# powermax.net
KiCad netlist of a schematic drawn in EAGLE
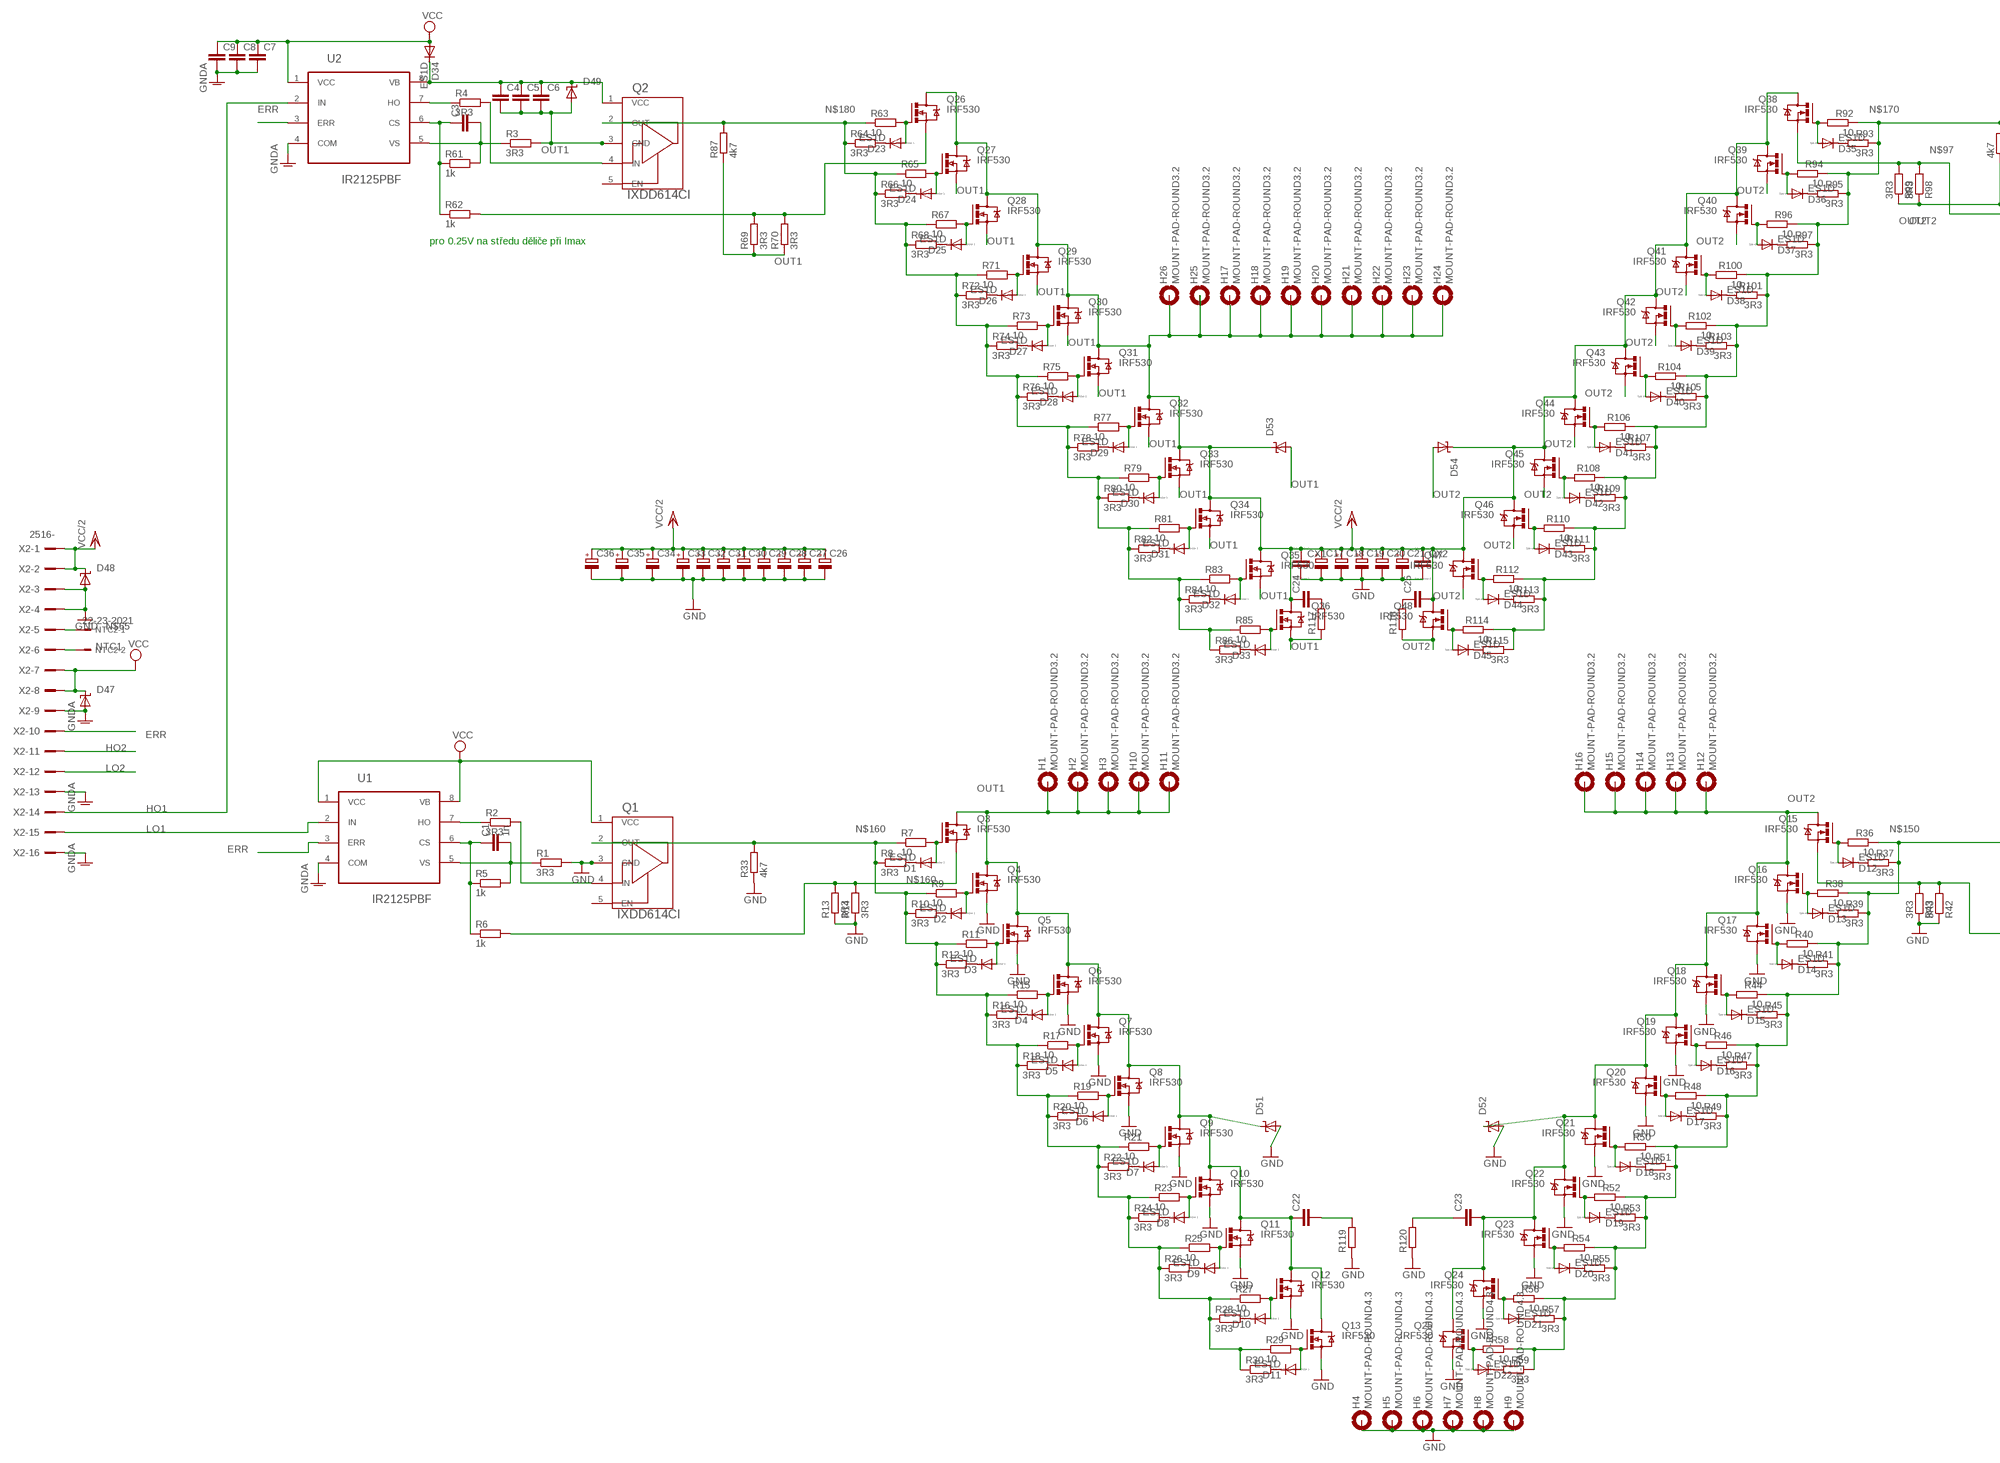
[diagram p0: schematic, sheet 1, part 1 of 2]
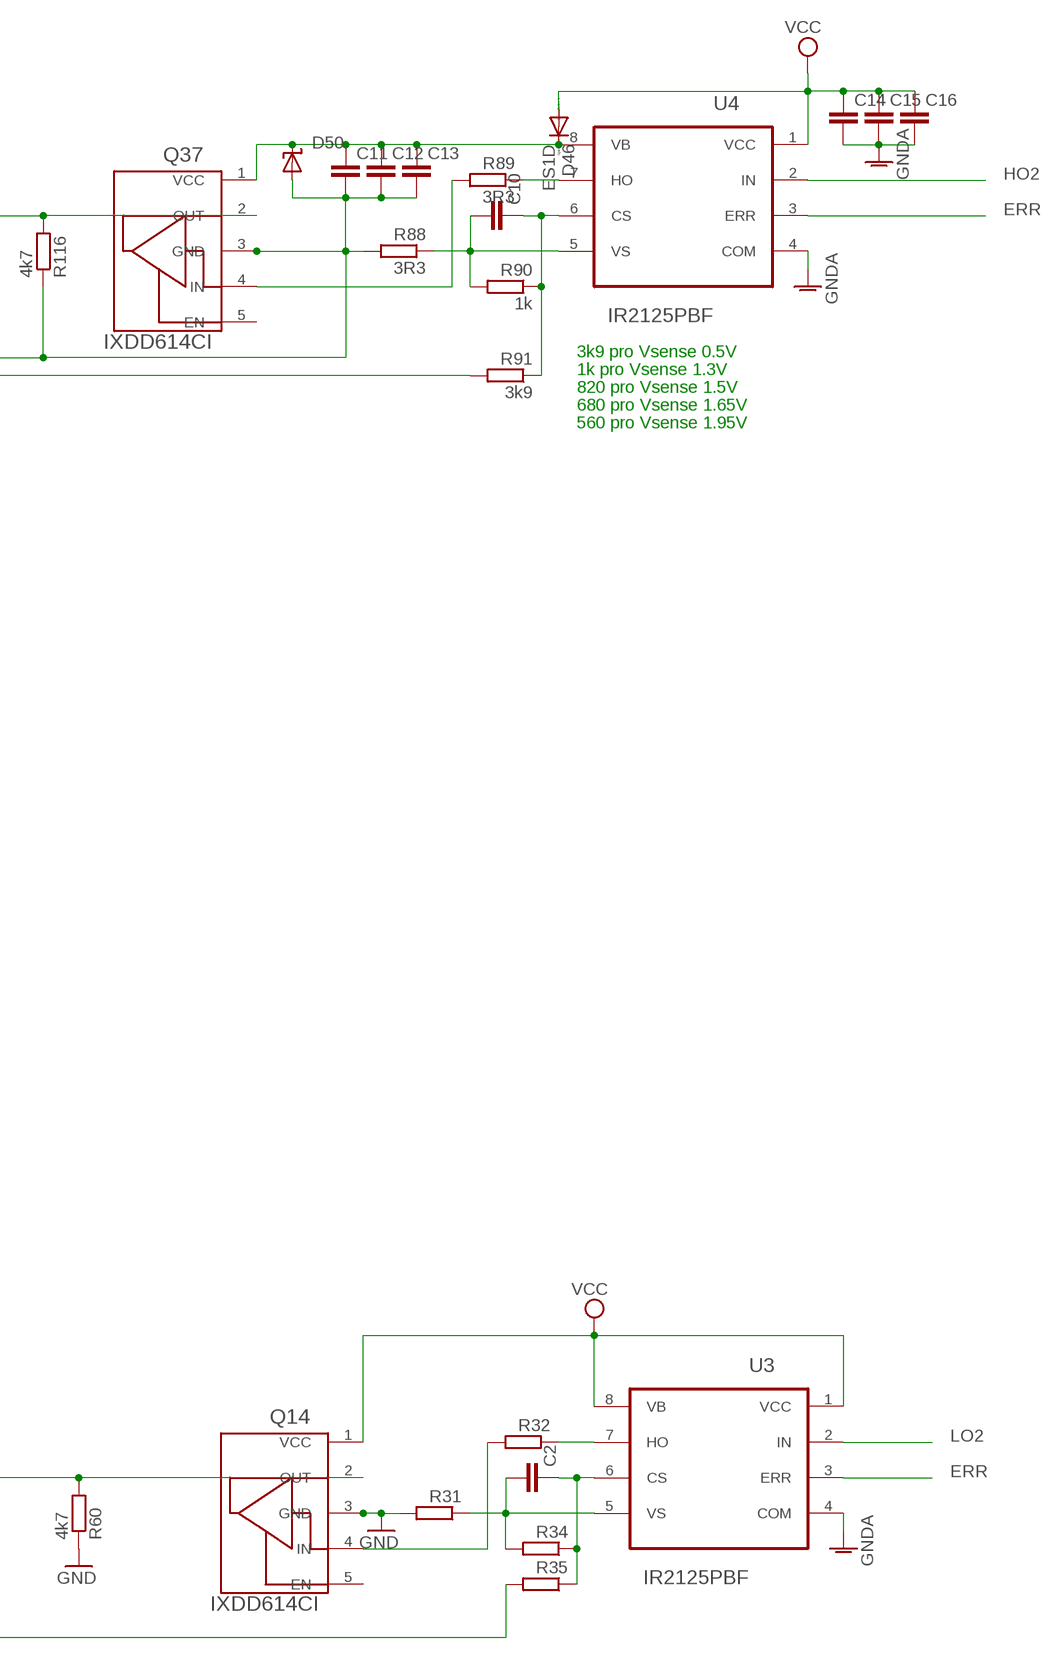
[diagram p1: schematic, sheet 1, part 2 of 2]

(export (version "E")
  (design (tool "Eeschema 10.0.6"))
  (components
    (comp (ref "C1")
      (value "1n")
      (footprint "eagle-import:C0805")
      (libsource (lib "eagle-import") (part "C-EUC0805"))
    )
    (comp (ref "C2")
      (value "C-EUC0805")
      (footprint "eagle-import:C0805")
      (libsource (lib "eagle-import") (part "C-EUC0805"))
    )
    (comp (ref "C3")
      (value "C-EUC0805")
      (footprint "eagle-import:C0805")
      (libsource (lib "eagle-import") (part "C-EUC0805"))
    )
    (comp (ref "C4")
      (value "C-EUC1210")
      (footprint "eagle-import:C1210")
      (libsource (lib "eagle-import") (part "C-EUC1210"))
    )
    (comp (ref "C5")
      (value "C-EUC1210")
      (footprint "eagle-import:C1210")
      (libsource (lib "eagle-import") (part "C-EUC1210"))
    )
    (comp (ref "C6")
      (value "C-EUC1210")
      (footprint "eagle-import:C1210")
      (libsource (lib "eagle-import") (part "C-EUC1210"))
    )
    (comp (ref "C7")
      (value "C-EUC1210")
      (footprint "eagle-import:C1210")
      (libsource (lib "eagle-import") (part "C-EUC1210"))
    )
    (comp (ref "C8")
      (value "C-EUC1210")
      (footprint "eagle-import:C1210")
      (libsource (lib "eagle-import") (part "C-EUC1210"))
    )
    (comp (ref "C9")
      (value "C-EUC1210")
      (footprint "eagle-import:C1210")
      (libsource (lib "eagle-import") (part "C-EUC1210"))
    )
    (comp (ref "C10")
      (value "C-EUC0805")
      (footprint "eagle-import:C0805")
      (libsource (lib "eagle-import") (part "C-EUC0805"))
    )
    (comp (ref "C11")
      (value "C-EUC1210")
      (footprint "eagle-import:C1210")
      (libsource (lib "eagle-import") (part "C-EUC1210"))
    )
    (comp (ref "C12")
      (value "C-EUC1210")
      (footprint "eagle-import:C1210")
      (libsource (lib "eagle-import") (part "C-EUC1210"))
    )
    (comp (ref "C13")
      (value "C-EUC1210")
      (footprint "eagle-import:C1210")
      (libsource (lib "eagle-import") (part "C-EUC1210"))
    )
    (comp (ref "C14")
      (value "C-EUC1210")
      (footprint "eagle-import:C1210")
      (libsource (lib "eagle-import") (part "C-EUC1210"))
    )
    (comp (ref "C15")
      (value "C-EUC1210")
      (footprint "eagle-import:C1210")
      (libsource (lib "eagle-import") (part "C-EUC1210"))
    )
    (comp (ref "C16")
      (value "C-EUC1210")
      (footprint "eagle-import:C1210")
      (libsource (lib "eagle-import") (part "C-EUC1210"))
    )
    (comp (ref "C17")
      (value "CPOL-EUE10-35")
      (footprint "eagle-import:EB35D")
      (libsource (lib "eagle-import") (part "CPOL-EUE10-35"))
    )
    (comp (ref "C18")
      (value "CPOL-EUE10-35")
      (footprint "eagle-import:EB35D")
      (libsource (lib "eagle-import") (part "CPOL-EUE10-35"))
    )
    (comp (ref "C19")
      (value "CPOL-EUE10-35")
      (footprint "eagle-import:EB35D")
      (libsource (lib "eagle-import") (part "CPOL-EUE10-35"))
    )
    (comp (ref "C20")
      (value "CPOL-EUE10-35")
      (footprint "eagle-import:EB35D")
      (libsource (lib "eagle-import") (part "CPOL-EUE10-35"))
    )
    (comp (ref "C21")
      (value "CPOL-EUE10-35")
      (footprint "eagle-import:EB35D")
      (libsource (lib "eagle-import") (part "CPOL-EUE10-35"))
    )
    (comp (ref "C22")
      (value "C-EU225-113X268")
      (footprint "eagle-import:C225-113X268")
      (libsource (lib "eagle-import") (part "C-EU225-113X268"))
    )
    (comp (ref "C23")
      (value "C-EU225-113X268")
      (footprint "eagle-import:C225-113X268")
      (libsource (lib "eagle-import") (part "C-EU225-113X268"))
    )
    (comp (ref "C24")
      (value "C-EU225-113X268")
      (footprint "eagle-import:C225-113X268")
      (libsource (lib "eagle-import") (part "C-EU225-113X268"))
    )
    (comp (ref "C25")
      (value "C-EU225-113X268")
      (footprint "eagle-import:C225-113X268")
      (libsource (lib "eagle-import") (part "C-EU225-113X268"))
    )
    (comp (ref "C26")
      (value "CPOL-EUE7.5-18")
      (footprint "eagle-import:E7,5-18")
      (libsource (lib "eagle-import") (part "CPOL-EUE7.5-18"))
    )
    (comp (ref "C27")
      (value "CPOL-EUE7.5-18")
      (footprint "eagle-import:E7,5-18")
      (libsource (lib "eagle-import") (part "CPOL-EUE7.5-18"))
    )
    (comp (ref "C28")
      (value "CPOL-EUE7.5-18")
      (footprint "eagle-import:E7,5-18")
      (libsource (lib "eagle-import") (part "CPOL-EUE7.5-18"))
    )
    (comp (ref "C29")
      (value "CPOL-EUE7.5-18")
      (footprint "eagle-import:E7,5-18")
      (libsource (lib "eagle-import") (part "CPOL-EUE7.5-18"))
    )
    (comp (ref "C30")
      (value "CPOL-EUE7.5-18")
      (footprint "eagle-import:E7,5-18")
      (libsource (lib "eagle-import") (part "CPOL-EUE7.5-18"))
    )
    (comp (ref "C31")
      (value "CPOL-EUE7.5-18")
      (footprint "eagle-import:E7,5-18")
      (libsource (lib "eagle-import") (part "CPOL-EUE7.5-18"))
    )
    (comp (ref "C32")
      (value "CPOL-EUE7.5-18")
      (footprint "eagle-import:E7,5-18")
      (libsource (lib "eagle-import") (part "CPOL-EUE7.5-18"))
    )
    (comp (ref "C33")
      (value "CPOL-EUE7.5-18")
      (footprint "eagle-import:E7,5-18")
      (libsource (lib "eagle-import") (part "CPOL-EUE7.5-18"))
    )
    (comp (ref "C34")
      (value "CPOL-EUE7.5-18")
      (footprint "eagle-import:E7,5-18")
      (libsource (lib "eagle-import") (part "CPOL-EUE7.5-18"))
    )
    (comp (ref "C35")
      (value "CPOL-EUE7.5-18")
      (footprint "eagle-import:E7,5-18")
      (libsource (lib "eagle-import") (part "CPOL-EUE7.5-18"))
    )
    (comp (ref "C36")
      (value "CPOL-EUE7.5-18")
      (footprint "eagle-import:E7,5-18")
      (libsource (lib "eagle-import") (part "CPOL-EUE7.5-18"))
    )
    (comp (ref "CX1")
      (value "CXXC27B11")
      (footprint "eagle-import:XC27B11")
      (libsource (lib "eagle-import") (part "CXXC27B11"))
    )
    (comp (ref "CX2")
      (value "CXXC27B11")
      (footprint "eagle-import:XC27B11")
      (libsource (lib "eagle-import") (part "CXXC27B11"))
    )
    (comp (ref "D1")
      (value "ES1D")
      (footprint "eagle-import:SOD80C")
      (libsource (lib "eagle-import") (part "PMLL4150"))
    )
    (comp (ref "D2")
      (value "ES1D")
      (footprint "eagle-import:SOD80C")
      (libsource (lib "eagle-import") (part "PMLL4150"))
    )
    (comp (ref "D3")
      (value "ES1D")
      (footprint "eagle-import:SOD80C")
      (libsource (lib "eagle-import") (part "PMLL4150"))
    )
    (comp (ref "D4")
      (value "ES1D")
      (footprint "eagle-import:SOD80C")
      (libsource (lib "eagle-import") (part "PMLL4150"))
    )
    (comp (ref "D5")
      (value "ES1D")
      (footprint "eagle-import:SOD80C")
      (libsource (lib "eagle-import") (part "PMLL4150"))
    )
    (comp (ref "D6")
      (value "ES1D")
      (footprint "eagle-import:SOD80C")
      (libsource (lib "eagle-import") (part "PMLL4150"))
    )
    (comp (ref "D7")
      (value "ES1D")
      (footprint "eagle-import:SOD80C")
      (libsource (lib "eagle-import") (part "PMLL4150"))
    )
    (comp (ref "D8")
      (value "ES1D")
      (footprint "eagle-import:SOD80C")
      (libsource (lib "eagle-import") (part "PMLL4150"))
    )
    (comp (ref "D9")
      (value "ES1D")
      (footprint "eagle-import:SOD80C")
      (libsource (lib "eagle-import") (part "PMLL4150"))
    )
    (comp (ref "D10")
      (value "ES1D")
      (footprint "eagle-import:SOD80C")
      (libsource (lib "eagle-import") (part "PMLL4150"))
    )
    (comp (ref "D11")
      (value "ES1D")
      (footprint "eagle-import:SOD80C")
      (libsource (lib "eagle-import") (part "PMLL4150"))
    )
    (comp (ref "D12")
      (value "ES1D")
      (footprint "eagle-import:SOD80C")
      (libsource (lib "eagle-import") (part "PMLL4150"))
    )
    (comp (ref "D13")
      (value "ES1D")
      (footprint "eagle-import:SOD80C")
      (libsource (lib "eagle-import") (part "PMLL4150"))
    )
    (comp (ref "D14")
      (value "ES1D")
      (footprint "eagle-import:SOD80C")
      (libsource (lib "eagle-import") (part "PMLL4150"))
    )
    (comp (ref "D15")
      (value "ES1D")
      (footprint "eagle-import:SOD80C")
      (libsource (lib "eagle-import") (part "PMLL4150"))
    )
    (comp (ref "D16")
      (value "ES1D")
      (footprint "eagle-import:SOD80C")
      (libsource (lib "eagle-import") (part "PMLL4150"))
    )
    (comp (ref "D17")
      (value "ES1D")
      (footprint "eagle-import:SOD80C")
      (libsource (lib "eagle-import") (part "PMLL4150"))
    )
    (comp (ref "D18")
      (value "ES1D")
      (footprint "eagle-import:SOD80C")
      (libsource (lib "eagle-import") (part "PMLL4150"))
    )
    (comp (ref "D19")
      (value "ES1D")
      (footprint "eagle-import:SOD80C")
      (libsource (lib "eagle-import") (part "PMLL4150"))
    )
    (comp (ref "D20")
      (value "ES1D")
      (footprint "eagle-import:SOD80C")
      (libsource (lib "eagle-import") (part "PMLL4150"))
    )
    (comp (ref "D21")
      (value "ES1D")
      (footprint "eagle-import:SOD80C")
      (libsource (lib "eagle-import") (part "PMLL4150"))
    )
    (comp (ref "D22")
      (value "ES1D")
      (footprint "eagle-import:SOD80C")
      (libsource (lib "eagle-import") (part "PMLL4150"))
    )
    (comp (ref "D23")
      (value "ES1D")
      (footprint "eagle-import:SOD80C")
      (libsource (lib "eagle-import") (part "PMLL4150"))
    )
    (comp (ref "D24")
      (value "ES1D")
      (footprint "eagle-import:SOD80C")
      (libsource (lib "eagle-import") (part "PMLL4150"))
    )
    (comp (ref "D25")
      (value "ES1D")
      (footprint "eagle-import:SOD80C")
      (libsource (lib "eagle-import") (part "PMLL4150"))
    )
    (comp (ref "D26")
      (value "ES1D")
      (footprint "eagle-import:SOD80C")
      (libsource (lib "eagle-import") (part "PMLL4150"))
    )
    (comp (ref "D27")
      (value "ES1D")
      (footprint "eagle-import:SOD80C")
      (libsource (lib "eagle-import") (part "PMLL4150"))
    )
    (comp (ref "D28")
      (value "ES1D")
      (footprint "eagle-import:SOD80C")
      (libsource (lib "eagle-import") (part "PMLL4150"))
    )
    (comp (ref "D29")
      (value "ES1D")
      (footprint "eagle-import:SOD80C")
      (libsource (lib "eagle-import") (part "PMLL4150"))
    )
    (comp (ref "D30")
      (value "ES1D")
      (footprint "eagle-import:SOD80C")
      (libsource (lib "eagle-import") (part "PMLL4150"))
    )
    (comp (ref "D31")
      (value "ES1D")
      (footprint "eagle-import:SOD80C")
      (libsource (lib "eagle-import") (part "PMLL4150"))
    )
    (comp (ref "D32")
      (value "ES1D")
      (footprint "eagle-import:SOD80C")
      (libsource (lib "eagle-import") (part "PMLL4150"))
    )
    (comp (ref "D33")
      (value "ES1D")
      (footprint "eagle-import:SOD80C")
      (libsource (lib "eagle-import") (part "PMLL4150"))
    )
    (comp (ref "D34")
      (value "ES1D")
      (footprint "eagle-import:SOD80C")
      (libsource (lib "eagle-import") (part "PMLL4150"))
    )
    (comp (ref "D35")
      (value "ES1D")
      (footprint "eagle-import:SOD80C")
      (libsource (lib "eagle-import") (part "PMLL4150"))
    )
    (comp (ref "D36")
      (value "ES1D")
      (footprint "eagle-import:SOD80C")
      (libsource (lib "eagle-import") (part "PMLL4150"))
    )
    (comp (ref "D37")
      (value "ES1D")
      (footprint "eagle-import:SOD80C")
      (libsource (lib "eagle-import") (part "PMLL4150"))
    )
    (comp (ref "D38")
      (value "ES1D")
      (footprint "eagle-import:SOD80C")
      (libsource (lib "eagle-import") (part "PMLL4150"))
    )
    (comp (ref "D39")
      (value "ES1D")
      (footprint "eagle-import:SOD80C")
      (libsource (lib "eagle-import") (part "PMLL4150"))
    )
    (comp (ref "D40")
      (value "ES1D")
      (footprint "eagle-import:SOD80C")
      (libsource (lib "eagle-import") (part "PMLL4150"))
    )
    (comp (ref "D41")
      (value "ES1D")
      (footprint "eagle-import:SOD80C")
      (libsource (lib "eagle-import") (part "PMLL4150"))
    )
    (comp (ref "D42")
      (value "ES1D")
      (footprint "eagle-import:SOD80C")
      (libsource (lib "eagle-import") (part "PMLL4150"))
    )
    (comp (ref "D43")
      (value "ES1D")
      (footprint "eagle-import:SOD80C")
      (libsource (lib "eagle-import") (part "PMLL4150"))
    )
    (comp (ref "D44")
      (value "ES1D")
      (footprint "eagle-import:SOD80C")
      (libsource (lib "eagle-import") (part "PMLL4150"))
    )
    (comp (ref "D45")
      (value "ES1D")
      (footprint "eagle-import:SOD80C")
      (libsource (lib "eagle-import") (part "PMLL4150"))
    )
    (comp (ref "D46")
      (value "ES1D")
      (footprint "eagle-import:SOD80C")
      (libsource (lib "eagle-import") (part "PMLL4150"))
    )
    (comp (ref "D47")
      (value "SUPPRESSOR-SMBJ")
      (footprint "eagle-import:SMBJ")
      (libsource (lib "eagle-import") (part "SUPPRESSOR-SMBJ"))
    )
    (comp (ref "D48")
      (value "SUPPRESSOR-SMBJ")
      (footprint "eagle-import:SMBJ")
      (libsource (lib "eagle-import") (part "SUPPRESSOR-SMBJ"))
    )
    (comp (ref "D49")
      (value "SUPPRESSOR-SMBJ")
      (footprint "eagle-import:SMBJ")
      (libsource (lib "eagle-import") (part "SUPPRESSOR-SMBJ"))
    )
    (comp (ref "D50")
      (value "SUPPRESSOR-SMBJ")
      (footprint "eagle-import:SMBJ")
      (libsource (lib "eagle-import") (part "SUPPRESSOR-SMBJ"))
    )
    (comp (ref "D51")
      (value "SUPPRESSOR-SMBJ")
      (footprint "eagle-import:SMBJ")
      (libsource (lib "eagle-import") (part "SUPPRESSOR-SMBJ"))
    )
    (comp (ref "D52")
      (value "SUPPRESSOR-SMBJ")
      (footprint "eagle-import:SMBJ")
      (libsource (lib "eagle-import") (part "SUPPRESSOR-SMBJ"))
    )
    (comp (ref "D53")
      (value "SUPPRESSOR-SMBJ")
      (footprint "eagle-import:SMBJ")
      (libsource (lib "eagle-import") (part "SUPPRESSOR-SMBJ"))
    )
    (comp (ref "D54")
      (value "SUPPRESSOR-SMBJ")
      (footprint "eagle-import:SMBJ")
      (libsource (lib "eagle-import") (part "SUPPRESSOR-SMBJ"))
    )
    (comp (ref "H1")
      (value "MOUNT-PAD-ROUND3.2")
      (footprint "eagle-import:3,2-PAD")
      (libsource (lib "eagle-import") (part "MOUNT-PAD-ROUND3.2"))
    )
    (comp (ref "H2")
      (value "MOUNT-PAD-ROUND3.2")
      (footprint "eagle-import:3,2-PAD")
      (libsource (lib "eagle-import") (part "MOUNT-PAD-ROUND3.2"))
    )
    (comp (ref "H3")
      (value "MOUNT-PAD-ROUND3.2")
      (footprint "eagle-import:3,2-PAD")
      (libsource (lib "eagle-import") (part "MOUNT-PAD-ROUND3.2"))
    )
    (comp (ref "H4")
      (value "MOUNT-PAD-ROUND4.3")
      (footprint "eagle-import:4,3-PAD")
      (libsource (lib "eagle-import") (part "MOUNT-PAD-ROUND4.3"))
    )
    (comp (ref "H5")
      (value "MOUNT-PAD-ROUND4.3")
      (footprint "eagle-import:4,3-PAD")
      (libsource (lib "eagle-import") (part "MOUNT-PAD-ROUND4.3"))
    )
    (comp (ref "H6")
      (value "MOUNT-PAD-ROUND4.3")
      (footprint "eagle-import:4,3-PAD")
      (libsource (lib "eagle-import") (part "MOUNT-PAD-ROUND4.3"))
    )
    (comp (ref "H7")
      (value "MOUNT-PAD-ROUND4.3")
      (footprint "eagle-import:4,3-PAD")
      (libsource (lib "eagle-import") (part "MOUNT-PAD-ROUND4.3"))
    )
    (comp (ref "H8")
      (value "MOUNT-PAD-ROUND4.3")
      (footprint "eagle-import:4,3-PAD")
      (libsource (lib "eagle-import") (part "MOUNT-PAD-ROUND4.3"))
    )
    (comp (ref "H9")
      (value "MOUNT-PAD-ROUND4.3")
      (footprint "eagle-import:4,3-PAD")
      (libsource (lib "eagle-import") (part "MOUNT-PAD-ROUND4.3"))
    )
    (comp (ref "H10")
      (value "MOUNT-PAD-ROUND3.2")
      (footprint "eagle-import:3,2-PAD")
      (libsource (lib "eagle-import") (part "MOUNT-PAD-ROUND3.2"))
    )
    (comp (ref "H11")
      (value "MOUNT-PAD-ROUND3.2")
      (footprint "eagle-import:3,2-PAD")
      (libsource (lib "eagle-import") (part "MOUNT-PAD-ROUND3.2"))
    )
    (comp (ref "H12")
      (value "MOUNT-PAD-ROUND3.2")
      (footprint "eagle-import:3,2-PAD")
      (libsource (lib "eagle-import") (part "MOUNT-PAD-ROUND3.2"))
    )
    (comp (ref "H13")
      (value "MOUNT-PAD-ROUND3.2")
      (footprint "eagle-import:3,2-PAD")
      (libsource (lib "eagle-import") (part "MOUNT-PAD-ROUND3.2"))
    )
    (comp (ref "H14")
      (value "MOUNT-PAD-ROUND3.2")
      (footprint "eagle-import:3,2-PAD")
      (libsource (lib "eagle-import") (part "MOUNT-PAD-ROUND3.2"))
    )
    (comp (ref "H15")
      (value "MOUNT-PAD-ROUND3.2")
      (footprint "eagle-import:3,2-PAD")
      (libsource (lib "eagle-import") (part "MOUNT-PAD-ROUND3.2"))
    )
    (comp (ref "H16")
      (value "MOUNT-PAD-ROUND3.2")
      (footprint "eagle-import:3,2-PAD")
      (libsource (lib "eagle-import") (part "MOUNT-PAD-ROUND3.2"))
    )
    (comp (ref "H17")
      (value "MOUNT-PAD-ROUND3.2")
      (footprint "eagle-import:3,2-PAD")
      (libsource (lib "eagle-import") (part "MOUNT-PAD-ROUND3.2"))
    )
    (comp (ref "H18")
      (value "MOUNT-PAD-ROUND3.2")
      (footprint "eagle-import:3,2-PAD")
      (libsource (lib "eagle-import") (part "MOUNT-PAD-ROUND3.2"))
    )
    (comp (ref "H19")
      (value "MOUNT-PAD-ROUND3.2")
      (footprint "eagle-import:3,2-PAD")
      (libsource (lib "eagle-import") (part "MOUNT-PAD-ROUND3.2"))
    )
    (comp (ref "H20")
      (value "MOUNT-PAD-ROUND3.2")
      (footprint "eagle-import:3,2-PAD")
      (libsource (lib "eagle-import") (part "MOUNT-PAD-ROUND3.2"))
    )
    (comp (ref "H21")
      (value "MOUNT-PAD-ROUND3.2")
      (footprint "eagle-import:3,2-PAD")
      (libsource (lib "eagle-import") (part "MOUNT-PAD-ROUND3.2"))
    )
    (comp (ref "H22")
      (value "MOUNT-PAD-ROUND3.2")
      (footprint "eagle-import:3,2-PAD")
      (libsource (lib "eagle-import") (part "MOUNT-PAD-ROUND3.2"))
    )
    (comp (ref "H23")
      (value "MOUNT-PAD-ROUND3.2")
      (footprint "eagle-import:3,2-PAD")
      (libsource (lib "eagle-import") (part "MOUNT-PAD-ROUND3.2"))
    )
    (comp (ref "H24")
      (value "MOUNT-PAD-ROUND3.2")
      (footprint "eagle-import:3,2-PAD")
      (libsource (lib "eagle-import") (part "MOUNT-PAD-ROUND3.2"))
    )
    (comp (ref "H25")
      (value "MOUNT-PAD-ROUND3.2")
      (footprint "eagle-import:3,2-PAD")
      (libsource (lib "eagle-import") (part "MOUNT-PAD-ROUND3.2"))
    )
    (comp (ref "H26")
      (value "MOUNT-PAD-ROUND3.2")
      (footprint "eagle-import:3,2-PAD")
      (libsource (lib "eagle-import") (part "MOUNT-PAD-ROUND3.2"))
    )
    (comp (ref "NTC2")
      (value "22-23-2021")
      (footprint "eagle-import:22-23-2021")
      (fields (field (name "MF") "MOLEX"))
      (libsource (lib "eagle-import") (part "22-23-2021"))
    )
    (comp (ref "Q1")
      (value "IXDD614CI")
      (footprint "eagle-import:TO-220-5")
      (fields (field (name "MF") "IXYS Integrated"))
      (libsource (lib "eagle-import") (part "IXDD614CI"))
    )
    (comp (ref "Q2")
      (value "IXDD614CI")
      (footprint "eagle-import:TO-220-5")
      (fields (field (name "MF") "IXYS Integrated"))
      (libsource (lib "eagle-import") (part "IXDD614CI"))
    )
    (comp (ref "Q3")
      (value "IRF530")
      (footprint "eagle-import:TO220BV")
      (libsource (lib "eagle-import") (part "IRF530"))
    )
    (comp (ref "Q4")
      (value "IRF530")
      (footprint "eagle-import:TO220BV")
      (libsource (lib "eagle-import") (part "IRF530"))
    )
    (comp (ref "Q5")
      (value "IRF530")
      (footprint "eagle-import:TO220BV")
      (libsource (lib "eagle-import") (part "IRF530"))
    )
    (comp (ref "Q6")
      (value "IRF530")
      (footprint "eagle-import:TO220BV")
      (libsource (lib "eagle-import") (part "IRF530"))
    )
    (comp (ref "Q7")
      (value "IRF530")
      (footprint "eagle-import:TO220BV")
      (libsource (lib "eagle-import") (part "IRF530"))
    )
    (comp (ref "Q8")
      (value "IRF530")
      (footprint "eagle-import:TO220BV")
      (libsource (lib "eagle-import") (part "IRF530"))
    )
    (comp (ref "Q9")
      (value "IRF530")
      (footprint "eagle-import:TO220BV")
      (libsource (lib "eagle-import") (part "IRF530"))
    )
    (comp (ref "Q10")
      (value "IRF530")
      (footprint "eagle-import:TO220BV")
      (libsource (lib "eagle-import") (part "IRF530"))
    )
    (comp (ref "Q11")
      (value "IRF530")
      (footprint "eagle-import:TO220BV")
      (libsource (lib "eagle-import") (part "IRF530"))
    )
    (comp (ref "Q12")
      (value "IRF530")
      (footprint "eagle-import:TO220BV")
      (libsource (lib "eagle-import") (part "IRF530"))
    )
    (comp (ref "Q13")
      (value "IRF530")
      (footprint "eagle-import:TO220BV")
      (libsource (lib "eagle-import") (part "IRF530"))
    )
    (comp (ref "Q14")
      (value "IXDD614CI")
      (footprint "eagle-import:TO-220-5")
      (fields (field (name "MF") "IXYS Integrated"))
      (libsource (lib "eagle-import") (part "IXDD614CI"))
    )
    (comp (ref "Q15")
      (value "IRF530")
      (footprint "eagle-import:TO220BV")
      (libsource (lib "eagle-import") (part "IRF530"))
    )
    (comp (ref "Q16")
      (value "IRF530")
      (footprint "eagle-import:TO220BV")
      (libsource (lib "eagle-import") (part "IRF530"))
    )
    (comp (ref "Q17")
      (value "IRF530")
      (footprint "eagle-import:TO220BV")
      (libsource (lib "eagle-import") (part "IRF530"))
    )
    (comp (ref "Q18")
      (value "IRF530")
      (footprint "eagle-import:TO220BV")
      (libsource (lib "eagle-import") (part "IRF530"))
    )
    (comp (ref "Q19")
      (value "IRF530")
      (footprint "eagle-import:TO220BV")
      (libsource (lib "eagle-import") (part "IRF530"))
    )
    (comp (ref "Q20")
      (value "IRF530")
      (footprint "eagle-import:TO220BV")
      (libsource (lib "eagle-import") (part "IRF530"))
    )
    (comp (ref "Q21")
      (value "IRF530")
      (footprint "eagle-import:TO220BV")
      (libsource (lib "eagle-import") (part "IRF530"))
    )
    (comp (ref "Q22")
      (value "IRF530")
      (footprint "eagle-import:TO220BV")
      (libsource (lib "eagle-import") (part "IRF530"))
    )
    (comp (ref "Q23")
      (value "IRF530")
      (footprint "eagle-import:TO220BV")
      (libsource (lib "eagle-import") (part "IRF530"))
    )
    (comp (ref "Q24")
      (value "IRF530")
      (footprint "eagle-import:TO220BV")
      (libsource (lib "eagle-import") (part "IRF530"))
    )
    (comp (ref "Q25")
      (value "IRF530")
      (footprint "eagle-import:TO220BV")
      (libsource (lib "eagle-import") (part "IRF530"))
    )
    (comp (ref "Q26")
      (value "IRF530")
      (footprint "eagle-import:TO220BV")
      (libsource (lib "eagle-import") (part "IRF530"))
    )
    (comp (ref "Q27")
      (value "IRF530")
      (footprint "eagle-import:TO220BV")
      (libsource (lib "eagle-import") (part "IRF530"))
    )
    (comp (ref "Q28")
      (value "IRF530")
      (footprint "eagle-import:TO220BV")
      (libsource (lib "eagle-import") (part "IRF530"))
    )
    (comp (ref "Q29")
      (value "IRF530")
      (footprint "eagle-import:TO220BV")
      (libsource (lib "eagle-import") (part "IRF530"))
    )
    (comp (ref "Q30")
      (value "IRF530")
      (footprint "eagle-import:TO220BV")
      (libsource (lib "eagle-import") (part "IRF530"))
    )
    (comp (ref "Q31")
      (value "IRF530")
      (footprint "eagle-import:TO220BV")
      (libsource (lib "eagle-import") (part "IRF530"))
    )
    (comp (ref "Q32")
      (value "IRF530")
      (footprint "eagle-import:TO220BV")
      (libsource (lib "eagle-import") (part "IRF530"))
    )
    (comp (ref "Q33")
      (value "IRF530")
      (footprint "eagle-import:TO220BV")
      (libsource (lib "eagle-import") (part "IRF530"))
    )
    (comp (ref "Q34")
      (value "IRF530")
      (footprint "eagle-import:TO220BV")
      (libsource (lib "eagle-import") (part "IRF530"))
    )
    (comp (ref "Q35")
      (value "IRF530")
      (footprint "eagle-import:TO220BV")
      (libsource (lib "eagle-import") (part "IRF530"))
    )
    (comp (ref "Q36")
      (value "IRF530")
      (footprint "eagle-import:TO220BV")
      (libsource (lib "eagle-import") (part "IRF530"))
    )
    (comp (ref "Q37")
      (value "IXDD614CI")
      (footprint "eagle-import:TO-220-5")
      (fields (field (name "MF") "IXYS Integrated"))
      (libsource (lib "eagle-import") (part "IXDD614CI"))
    )
    (comp (ref "Q38")
      (value "IRF530")
      (footprint "eagle-import:TO220BV")
      (libsource (lib "eagle-import") (part "IRF530"))
    )
    (comp (ref "Q39")
      (value "IRF530")
      (footprint "eagle-import:TO220BV")
      (libsource (lib "eagle-import") (part "IRF530"))
    )
    (comp (ref "Q40")
      (value "IRF530")
      (footprint "eagle-import:TO220BV")
      (libsource (lib "eagle-import") (part "IRF530"))
    )
    (comp (ref "Q41")
      (value "IRF530")
      (footprint "eagle-import:TO220BV")
      (libsource (lib "eagle-import") (part "IRF530"))
    )
    (comp (ref "Q42")
      (value "IRF530")
      (footprint "eagle-import:TO220BV")
      (libsource (lib "eagle-import") (part "IRF530"))
    )
    (comp (ref "Q43")
      (value "IRF530")
      (footprint "eagle-import:TO220BV")
      (libsource (lib "eagle-import") (part "IRF530"))
    )
    (comp (ref "Q44")
      (value "IRF530")
      (footprint "eagle-import:TO220BV")
      (libsource (lib "eagle-import") (part "IRF530"))
    )
    (comp (ref "Q45")
      (value "IRF530")
      (footprint "eagle-import:TO220BV")
      (libsource (lib "eagle-import") (part "IRF530"))
    )
    (comp (ref "Q46")
      (value "IRF530")
      (footprint "eagle-import:TO220BV")
      (libsource (lib "eagle-import") (part "IRF530"))
    )
    (comp (ref "Q47")
      (value "IRF530")
      (footprint "eagle-import:TO220BV")
      (libsource (lib "eagle-import") (part "IRF530"))
    )
    (comp (ref "Q48")
      (value "IRF530")
      (footprint "eagle-import:TO220BV")
      (libsource (lib "eagle-import") (part "IRF530"))
    )
    (comp (ref "R1")
      (value "3R3")
      (footprint "eagle-import:R0805")
      (libsource (lib "eagle-import") (part "R-EU_R0805"))
    )
    (comp (ref "R2")
      (value "3R3")
      (footprint "eagle-import:R0805")
      (libsource (lib "eagle-import") (part "R-EU_R0805"))
    )
    (comp (ref "R3")
      (value "3R3")
      (footprint "eagle-import:R0805")
      (libsource (lib "eagle-import") (part "R-EU_R0805"))
    )
    (comp (ref "R4")
      (value "3R3")
      (footprint "eagle-import:R0805")
      (libsource (lib "eagle-import") (part "R-EU_R0805"))
    )
    (comp (ref "R5")
      (value "1k")
      (footprint "eagle-import:R0805")
      (libsource (lib "eagle-import") (part "R-EU_R0805"))
    )
    (comp (ref "R6")
      (value "1k")
      (footprint "eagle-import:R0805")
      (libsource (lib "eagle-import") (part "R-EU_R0805"))
    )
    (comp (ref "R7")
      (value "10")
      (footprint "eagle-import:R0805")
      (libsource (lib "eagle-import") (part "R-EU_R0805"))
    )
    (comp (ref "R8")
      (value "3R3")
      (footprint "eagle-import:R0805")
      (libsource (lib "eagle-import") (part "R-EU_R0805"))
    )
    (comp (ref "R9")
      (value "10")
      (footprint "eagle-import:R0805")
      (libsource (lib "eagle-import") (part "R-EU_R0805"))
    )
    (comp (ref "R10")
      (value "3R3")
      (footprint "eagle-import:R0805")
      (libsource (lib "eagle-import") (part "R-EU_R0805"))
    )
    (comp (ref "R11")
      (value "10")
      (footprint "eagle-import:R0805")
      (libsource (lib "eagle-import") (part "R-EU_R0805"))
    )
    (comp (ref "R12")
      (value "3R3")
      (footprint "eagle-import:R0805")
      (libsource (lib "eagle-import") (part "R-EU_R0805"))
    )
    (comp (ref "R13")
      (value "3R3")
      (footprint "eagle-import:R0805")
      (libsource (lib "eagle-import") (part "R-EU_R0805"))
    )
    (comp (ref "R14")
      (value "3R3")
      (footprint "eagle-import:R0805")
      (libsource (lib "eagle-import") (part "R-EU_R0805"))
    )
    (comp (ref "R15")
      (value "10")
      (footprint "eagle-import:R0805")
      (libsource (lib "eagle-import") (part "R-EU_R0805"))
    )
    (comp (ref "R16")
      (value "3R3")
      (footprint "eagle-import:R0805")
      (libsource (lib "eagle-import") (part "R-EU_R0805"))
    )
    (comp (ref "R17")
      (value "10")
      (footprint "eagle-import:R0805")
      (libsource (lib "eagle-import") (part "R-EU_R0805"))
    )
    (comp (ref "R18")
      (value "3R3")
      (footprint "eagle-import:R0805")
      (libsource (lib "eagle-import") (part "R-EU_R0805"))
    )
    (comp (ref "R19")
      (value "10")
      (footprint "eagle-import:R0805")
      (libsource (lib "eagle-import") (part "R-EU_R0805"))
    )
    (comp (ref "R20")
      (value "3R3")
      (footprint "eagle-import:R0805")
      (libsource (lib "eagle-import") (part "R-EU_R0805"))
    )
    (comp (ref "R21")
      (value "10")
      (footprint "eagle-import:R0805")
      (libsource (lib "eagle-import") (part "R-EU_R0805"))
    )
    (comp (ref "R22")
      (value "3R3")
      (footprint "eagle-import:R0805")
      (libsource (lib "eagle-import") (part "R-EU_R0805"))
    )
    (comp (ref "R23")
      (value "10")
      (footprint "eagle-import:R0805")
      (libsource (lib "eagle-import") (part "R-EU_R0805"))
    )
    (comp (ref "R24")
      (value "3R3")
      (footprint "eagle-import:R0805")
      (libsource (lib "eagle-import") (part "R-EU_R0805"))
    )
    (comp (ref "R25")
      (value "10")
      (footprint "eagle-import:R0805")
      (libsource (lib "eagle-import") (part "R-EU_R0805"))
    )
    (comp (ref "R26")
      (value "3R3")
      (footprint "eagle-import:R0805")
      (libsource (lib "eagle-import") (part "R-EU_R0805"))
    )
    (comp (ref "R27")
      (value "10")
      (footprint "eagle-import:R0805")
      (libsource (lib "eagle-import") (part "R-EU_R0805"))
    )
    (comp (ref "R28")
      (value "3R3")
      (footprint "eagle-import:R0805")
      (libsource (lib "eagle-import") (part "R-EU_R0805"))
    )
    (comp (ref "R29")
      (value "10")
      (footprint "eagle-import:R0805")
      (libsource (lib "eagle-import") (part "R-EU_R0805"))
    )
    (comp (ref "R30")
      (value "3R3")
      (footprint "eagle-import:R0805")
      (libsource (lib "eagle-import") (part "R-EU_R0805"))
    )
    (comp (ref "R31")
      (value "R-EU_R0805")
      (footprint "eagle-import:R0805")
      (libsource (lib "eagle-import") (part "R-EU_R0805"))
    )
    (comp (ref "R32")
      (value "R-EU_R0805")
      (footprint "eagle-import:R0805")
      (libsource (lib "eagle-import") (part "R-EU_R0805"))
    )
    (comp (ref "R33")
      (value "4k7")
      (footprint "eagle-import:R0805")
      (libsource (lib "eagle-import") (part "R-EU_R0805"))
    )
    (comp (ref "R34")
      (value "R-EU_R0805")
      (footprint "eagle-import:R0805")
      (libsource (lib "eagle-import") (part "R-EU_R0805"))
    )
    (comp (ref "R35")
      (value "R-EU_R0805")
      (footprint "eagle-import:R0805")
      (libsource (lib "eagle-import") (part "R-EU_R0805"))
    )
    (comp (ref "R36")
      (value "10")
      (footprint "eagle-import:R0805")
      (libsource (lib "eagle-import") (part "R-EU_R0805"))
    )
    (comp (ref "R37")
      (value "3R3")
      (footprint "eagle-import:R0805")
      (libsource (lib "eagle-import") (part "R-EU_R0805"))
    )
    (comp (ref "R38")
      (value "10")
      (footprint "eagle-import:R0805")
      (libsource (lib "eagle-import") (part "R-EU_R0805"))
    )
    (comp (ref "R39")
      (value "3R3")
      (footprint "eagle-import:R0805")
      (libsource (lib "eagle-import") (part "R-EU_R0805"))
    )
    (comp (ref "R40")
      (value "10")
      (footprint "eagle-import:R0805")
      (libsource (lib "eagle-import") (part "R-EU_R0805"))
    )
    (comp (ref "R41")
      (value "3R3")
      (footprint "eagle-import:R0805")
      (libsource (lib "eagle-import") (part "R-EU_R0805"))
    )
    (comp (ref "R42")
      (value "3R3")
      (footprint "eagle-import:R0805")
      (libsource (lib "eagle-import") (part "R-EU_R0805"))
    )
    (comp (ref "R43")
      (value "3R3")
      (footprint "eagle-import:R0805")
      (libsource (lib "eagle-import") (part "R-EU_R0805"))
    )
    (comp (ref "R44")
      (value "10")
      (footprint "eagle-import:R0805")
      (libsource (lib "eagle-import") (part "R-EU_R0805"))
    )
    (comp (ref "R45")
      (value "3R3")
      (footprint "eagle-import:R0805")
      (libsource (lib "eagle-import") (part "R-EU_R0805"))
    )
    (comp (ref "R46")
      (value "10")
      (footprint "eagle-import:R0805")
      (libsource (lib "eagle-import") (part "R-EU_R0805"))
    )
    (comp (ref "R47")
      (value "3R3")
      (footprint "eagle-import:R0805")
      (libsource (lib "eagle-import") (part "R-EU_R0805"))
    )
    (comp (ref "R48")
      (value "10")
      (footprint "eagle-import:R0805")
      (libsource (lib "eagle-import") (part "R-EU_R0805"))
    )
    (comp (ref "R49")
      (value "3R3")
      (footprint "eagle-import:R0805")
      (libsource (lib "eagle-import") (part "R-EU_R0805"))
    )
    (comp (ref "R50")
      (value "10")
      (footprint "eagle-import:R0805")
      (libsource (lib "eagle-import") (part "R-EU_R0805"))
    )
    (comp (ref "R51")
      (value "3R3")
      (footprint "eagle-import:R0805")
      (libsource (lib "eagle-import") (part "R-EU_R0805"))
    )
    (comp (ref "R52")
      (value "10")
      (footprint "eagle-import:R0805")
      (libsource (lib "eagle-import") (part "R-EU_R0805"))
    )
    (comp (ref "R53")
      (value "3R3")
      (footprint "eagle-import:R0805")
      (libsource (lib "eagle-import") (part "R-EU_R0805"))
    )
    (comp (ref "R54")
      (value "10")
      (footprint "eagle-import:R0805")
      (libsource (lib "eagle-import") (part "R-EU_R0805"))
    )
    (comp (ref "R55")
      (value "3R3")
      (footprint "eagle-import:R0805")
      (libsource (lib "eagle-import") (part "R-EU_R0805"))
    )
    (comp (ref "R56")
      (value "10")
      (footprint "eagle-import:R0805")
      (libsource (lib "eagle-import") (part "R-EU_R0805"))
    )
    (comp (ref "R57")
      (value "3R3")
      (footprint "eagle-import:R0805")
      (libsource (lib "eagle-import") (part "R-EU_R0805"))
    )
    (comp (ref "R58")
      (value "10")
      (footprint "eagle-import:R0805")
      (libsource (lib "eagle-import") (part "R-EU_R0805"))
    )
    (comp (ref "R59")
      (value "3R3")
      (footprint "eagle-import:R0805")
      (libsource (lib "eagle-import") (part "R-EU_R0805"))
    )
    (comp (ref "R60")
      (value "4k7")
      (footprint "eagle-import:R0805")
      (libsource (lib "eagle-import") (part "R-EU_R0805"))
    )
    (comp (ref "R61")
      (value "1k")
      (footprint "eagle-import:R0805")
      (libsource (lib "eagle-import") (part "R-EU_R0805"))
    )
    (comp (ref "R62")
      (value "1k")
      (footprint "eagle-import:R0805")
      (libsource (lib "eagle-import") (part "R-EU_R0805"))
    )
    (comp (ref "R63")
      (value "10")
      (footprint "eagle-import:R0805")
      (libsource (lib "eagle-import") (part "R-EU_R0805"))
    )
    (comp (ref "R64")
      (value "3R3")
      (footprint "eagle-import:R0805")
      (libsource (lib "eagle-import") (part "R-EU_R0805"))
    )
    (comp (ref "R65")
      (value "10")
      (footprint "eagle-import:R0805")
      (libsource (lib "eagle-import") (part "R-EU_R0805"))
    )
    (comp (ref "R66")
      (value "3R3")
      (footprint "eagle-import:R0805")
      (libsource (lib "eagle-import") (part "R-EU_R0805"))
    )
    (comp (ref "R67")
      (value "10")
      (footprint "eagle-import:R0805")
      (libsource (lib "eagle-import") (part "R-EU_R0805"))
    )
    (comp (ref "R68")
      (value "3R3")
      (footprint "eagle-import:R0805")
      (libsource (lib "eagle-import") (part "R-EU_R0805"))
    )
    (comp (ref "R69")
      (value "3R3")
      (footprint "eagle-import:R0805")
      (libsource (lib "eagle-import") (part "R-EU_R0805"))
    )
    (comp (ref "R70")
      (value "3R3")
      (footprint "eagle-import:R0805")
      (libsource (lib "eagle-import") (part "R-EU_R0805"))
    )
    (comp (ref "R71")
      (value "10")
      (footprint "eagle-import:R0805")
      (libsource (lib "eagle-import") (part "R-EU_R0805"))
    )
    (comp (ref "R72")
      (value "3R3")
      (footprint "eagle-import:R0805")
      (libsource (lib "eagle-import") (part "R-EU_R0805"))
    )
    (comp (ref "R73")
      (value "10")
      (footprint "eagle-import:R0805")
      (libsource (lib "eagle-import") (part "R-EU_R0805"))
    )
    (comp (ref "R74")
      (value "3R3")
      (footprint "eagle-import:R0805")
      (libsource (lib "eagle-import") (part "R-EU_R0805"))
    )
    (comp (ref "R75")
      (value "10")
      (footprint "eagle-import:R0805")
      (libsource (lib "eagle-import") (part "R-EU_R0805"))
    )
    (comp (ref "R76")
      (value "3R3")
      (footprint "eagle-import:R0805")
      (libsource (lib "eagle-import") (part "R-EU_R0805"))
    )
    (comp (ref "R77")
      (value "10")
      (footprint "eagle-import:R0805")
      (libsource (lib "eagle-import") (part "R-EU_R0805"))
    )
    (comp (ref "R78")
      (value "3R3")
      (footprint "eagle-import:R0805")
      (libsource (lib "eagle-import") (part "R-EU_R0805"))
    )
    (comp (ref "R79")
      (value "10")
      (footprint "eagle-import:R0805")
      (libsource (lib "eagle-import") (part "R-EU_R0805"))
    )
    (comp (ref "R80")
      (value "3R3")
      (footprint "eagle-import:R0805")
      (libsource (lib "eagle-import") (part "R-EU_R0805"))
    )
    (comp (ref "R81")
      (value "10")
      (footprint "eagle-import:R0805")
      (libsource (lib "eagle-import") (part "R-EU_R0805"))
    )
    (comp (ref "R82")
      (value "3R3")
      (footprint "eagle-import:R0805")
      (libsource (lib "eagle-import") (part "R-EU_R0805"))
    )
    (comp (ref "R83")
      (value "10")
      (footprint "eagle-import:R0805")
      (libsource (lib "eagle-import") (part "R-EU_R0805"))
    )
    (comp (ref "R84")
      (value "3R3")
      (footprint "eagle-import:R0805")
      (libsource (lib "eagle-import") (part "R-EU_R0805"))
    )
    (comp (ref "R85")
      (value "10")
      (footprint "eagle-import:R0805")
      (libsource (lib "eagle-import") (part "R-EU_R0805"))
    )
    (comp (ref "R86")
      (value "3R3")
      (footprint "eagle-import:R0805")
      (libsource (lib "eagle-import") (part "R-EU_R0805"))
    )
    (comp (ref "R87")
      (value "4k7")
      (footprint "eagle-import:R0805")
      (libsource (lib "eagle-import") (part "R-EU_R0805"))
    )
    (comp (ref "R88")
      (value "3R3")
      (footprint "eagle-import:R0805")
      (libsource (lib "eagle-import") (part "R-EU_R0805"))
    )
    (comp (ref "R89")
      (value "3R3")
      (footprint "eagle-import:R0805")
      (libsource (lib "eagle-import") (part "R-EU_R0805"))
    )
    (comp (ref "R90")
      (value "1k")
      (footprint "eagle-import:R0805")
      (libsource (lib "eagle-import") (part "R-EU_R0805"))
    )
    (comp (ref "R91")
      (value "3k9")
      (footprint "eagle-import:R0805")
      (libsource (lib "eagle-import") (part "R-EU_R0805"))
    )
    (comp (ref "R92")
      (value "10")
      (footprint "eagle-import:R0805")
      (libsource (lib "eagle-import") (part "R-EU_R0805"))
    )
    (comp (ref "R93")
      (value "3R3")
      (footprint "eagle-import:R0805")
      (libsource (lib "eagle-import") (part "R-EU_R0805"))
    )
    (comp (ref "R94")
      (value "10")
      (footprint "eagle-import:R0805")
      (libsource (lib "eagle-import") (part "R-EU_R0805"))
    )
    (comp (ref "R95")
      (value "3R3")
      (footprint "eagle-import:R0805")
      (libsource (lib "eagle-import") (part "R-EU_R0805"))
    )
    (comp (ref "R96")
      (value "10")
      (footprint "eagle-import:R0805")
      (libsource (lib "eagle-import") (part "R-EU_R0805"))
    )
    (comp (ref "R97")
      (value "3R3")
      (footprint "eagle-import:R0805")
      (libsource (lib "eagle-import") (part "R-EU_R0805"))
    )
    (comp (ref "R98")
      (value "3R3")
      (footprint "eagle-import:R0805")
      (libsource (lib "eagle-import") (part "R-EU_R0805"))
    )
    (comp (ref "R99")
      (value "3R3")
      (footprint "eagle-import:R0805")
      (libsource (lib "eagle-import") (part "R-EU_R0805"))
    )
    (comp (ref "R100")
      (value "10")
      (footprint "eagle-import:R0805")
      (libsource (lib "eagle-import") (part "R-EU_R0805"))
    )
    (comp (ref "R101")
      (value "3R3")
      (footprint "eagle-import:R0805")
      (libsource (lib "eagle-import") (part "R-EU_R0805"))
    )
    (comp (ref "R102")
      (value "10")
      (footprint "eagle-import:R0805")
      (libsource (lib "eagle-import") (part "R-EU_R0805"))
    )
    (comp (ref "R103")
      (value "3R3")
      (footprint "eagle-import:R0805")
      (libsource (lib "eagle-import") (part "R-EU_R0805"))
    )
    (comp (ref "R104")
      (value "10")
      (footprint "eagle-import:R0805")
      (libsource (lib "eagle-import") (part "R-EU_R0805"))
    )
    (comp (ref "R105")
      (value "3R3")
      (footprint "eagle-import:R0805")
      (libsource (lib "eagle-import") (part "R-EU_R0805"))
    )
    (comp (ref "R106")
      (value "10")
      (footprint "eagle-import:R0805")
      (libsource (lib "eagle-import") (part "R-EU_R0805"))
    )
    (comp (ref "R107")
      (value "3R3")
      (footprint "eagle-import:R0805")
      (libsource (lib "eagle-import") (part "R-EU_R0805"))
    )
    (comp (ref "R108")
      (value "10")
      (footprint "eagle-import:R0805")
      (libsource (lib "eagle-import") (part "R-EU_R0805"))
    )
    (comp (ref "R109")
      (value "3R3")
      (footprint "eagle-import:R0805")
      (libsource (lib "eagle-import") (part "R-EU_R0805"))
    )
    (comp (ref "R110")
      (value "10")
      (footprint "eagle-import:R0805")
      (libsource (lib "eagle-import") (part "R-EU_R0805"))
    )
    (comp (ref "R111")
      (value "3R3")
      (footprint "eagle-import:R0805")
      (libsource (lib "eagle-import") (part "R-EU_R0805"))
    )
    (comp (ref "R112")
      (value "10")
      (footprint "eagle-import:R0805")
      (libsource (lib "eagle-import") (part "R-EU_R0805"))
    )
    (comp (ref "R113")
      (value "3R3")
      (footprint "eagle-import:R0805")
      (libsource (lib "eagle-import") (part "R-EU_R0805"))
    )
    (comp (ref "R114")
      (value "10")
      (footprint "eagle-import:R0805")
      (libsource (lib "eagle-import") (part "R-EU_R0805"))
    )
    (comp (ref "R115")
      (value "3R3")
      (footprint "eagle-import:R0805")
      (libsource (lib "eagle-import") (part "R-EU_R0805"))
    )
    (comp (ref "R116")
      (value "4k7")
      (footprint "eagle-import:R0805")
      (libsource (lib "eagle-import") (part "R-EU_R0805"))
    )
    (comp (ref "R117")
      (value "R-EU_0411/15")
      (footprint "eagle-import:0411_15")
      (libsource (lib "eagle-import") (part "R-EU_0411/15"))
    )
    (comp (ref "R118")
      (value "R-EU_0411/15")
      (footprint "eagle-import:0411_15")
      (libsource (lib "eagle-import") (part "R-EU_0411/15"))
    )
    (comp (ref "R119")
      (value "R-EU_0411/15")
      (footprint "eagle-import:0411_15")
      (libsource (lib "eagle-import") (part "R-EU_0411/15"))
    )
    (comp (ref "R120")
      (value "R-EU_0411/15")
      (footprint "eagle-import:0411_15")
      (libsource (lib "eagle-import") (part "R-EU_0411/15"))
    )
    (comp (ref "U1")
      (value "IR2125PBF")
      (footprint "eagle-import:DIP254P762X533-8")
      (libsource (lib "eagle-import") (part "IR2125PBF"))
    )
    (comp (ref "U2")
      (value "IR2125PBF")
      (footprint "eagle-import:DIP254P762X533-8")
      (libsource (lib "eagle-import") (part "IR2125PBF"))
    )
    (comp (ref "U3")
      (value "IR2125PBF")
      (footprint "eagle-import:DIP254P762X533-8")
      (libsource (lib "eagle-import") (part "IR2125PBF"))
    )
    (comp (ref "U4")
      (value "IR2125PBF")
      (footprint "eagle-import:DIP254P762X533-8")
      (libsource (lib "eagle-import") (part "IR2125PBF"))
    )
    (comp (ref "X2")
      (value "2516-")
      (footprint "eagle-import:PAK100_2500-16")
      (libsource (lib "eagle-import") (part "2516-"))
    )
  )
  (nets
    (net (code "1") (name "/ERR") (class "Default")
      (node (ref "U1") (pin "3") (pinfunction "ERR_3") (pintype "input"))
      (node (ref "U2") (pin "3") (pinfunction "ERR_3") (pintype "input"))
      (node (ref "U3") (pin "3") (pinfunction "ERR_3") (pintype "input"))
      (node (ref "U4") (pin "3") (pinfunction "ERR_3") (pintype "input"))
      (node (ref "X2") (pin "10") (pinfunction "KL_10") (pintype "passive"))
    )
    (net (code "2") (name "/HO1") (class "Default")
      (node (ref "U2") (pin "2") (pinfunction "IN_2") (pintype "input"))
      (node (ref "X2") (pin "14") (pinfunction "KL_14") (pintype "passive"))
    )
    (net (code "3") (name "/HO2") (class "Default")
      (node (ref "U4") (pin "2") (pinfunction "IN_2") (pintype "input"))
      (node (ref "X2") (pin "11") (pinfunction "KL_11") (pintype "passive"))
    )
    (net (code "4") (name "/LO1") (class "Default")
      (node (ref "U1") (pin "2") (pinfunction "IN_2") (pintype "input"))
      (node (ref "X2") (pin "15") (pinfunction "KL_15") (pintype "passive"))
    )
    (net (code "5") (name "/LO2") (class "Default")
      (node (ref "U3") (pin "2") (pinfunction "IN_2") (pintype "input"))
      (node (ref "X2") (pin "12") (pinfunction "KL_12") (pintype "passive"))
    )
    (net (code "6") (name "/N$65") (class "Default")
      (node (ref "NTC2") (pin "1") (pinfunction "S_1") (pintype "passive"))
      (node (ref "X2") (pin "5") (pinfunction "KL_5") (pintype "passive"))
    )
    (net (code "7") (name "/N$97") (class "Default")
      (node (ref "Q38") (pin "S") (pinfunction "S_S") (pintype "passive"))
      (node (ref "R91") (pin "2") (pinfunction "2_2") (pintype "passive"))
      (node (ref "R98") (pin "2") (pinfunction "2_2") (pintype "passive"))
      (node (ref "R99") (pin "2") (pinfunction "2_2") (pintype "passive"))
    )
    (net (code "8") (name "/N$150") (class "Default")
      (node (ref "Q14") (pin "2") (pinfunction "OUT_2") (pintype "output"))
      (node (ref "R36") (pin "1") (pinfunction "1_1") (pintype "passive"))
      (node (ref "R37") (pin "1") (pinfunction "1_1") (pintype "passive"))
      (node (ref "R38") (pin "1") (pinfunction "1_1") (pintype "passive"))
      (node (ref "R39") (pin "1") (pinfunction "1_1") (pintype "passive"))
      (node (ref "R40") (pin "1") (pinfunction "1_1") (pintype "passive"))
      (node (ref "R41") (pin "1") (pinfunction "1_1") (pintype "passive"))
      (node (ref "R44") (pin "1") (pinfunction "1_1") (pintype "passive"))
      (node (ref "R45") (pin "1") (pinfunction "1_1") (pintype "passive"))
      (node (ref "R46") (pin "1") (pinfunction "1_1") (pintype "passive"))
      (node (ref "R47") (pin "1") (pinfunction "1_1") (pintype "passive"))
      (node (ref "R48") (pin "1") (pinfunction "1_1") (pintype "passive"))
      (node (ref "R49") (pin "1") (pinfunction "1_1") (pintype "passive"))
      (node (ref "R50") (pin "1") (pinfunction "1_1") (pintype "passive"))
      (node (ref "R51") (pin "1") (pinfunction "1_1") (pintype "passive"))
      (node (ref "R52") (pin "1") (pinfunction "1_1") (pintype "passive"))
      (node (ref "R53") (pin "1") (pinfunction "1_1") (pintype "passive"))
      (node (ref "R54") (pin "1") (pinfunction "1_1") (pintype "passive"))
      (node (ref "R55") (pin "1") (pinfunction "1_1") (pintype "passive"))
      (node (ref "R56") (pin "1") (pinfunction "1_1") (pintype "passive"))
      (node (ref "R57") (pin "1") (pinfunction "1_1") (pintype "passive"))
      (node (ref "R58") (pin "1") (pinfunction "1_1") (pintype "passive"))
      (node (ref "R59") (pin "1") (pinfunction "1_1") (pintype "passive"))
      (node (ref "R60") (pin "2") (pinfunction "2_2") (pintype "passive"))
    )
    (net (code "9") (name "/N$160") (class "Default")
      (node (ref "Q1") (pin "2") (pinfunction "OUT_2") (pintype "output"))
      (node (ref "R10") (pin "1") (pinfunction "1_1") (pintype "passive"))
      (node (ref "R11") (pin "1") (pinfunction "1_1") (pintype "passive"))
      (node (ref "R12") (pin "1") (pinfunction "1_1") (pintype "passive"))
      (node (ref "R15") (pin "1") (pinfunction "1_1") (pintype "passive"))
      (node (ref "R16") (pin "1") (pinfunction "1_1") (pintype "passive"))
      (node (ref "R17") (pin "1") (pinfunction "1_1") (pintype "passive"))
      (node (ref "R18") (pin "1") (pinfunction "1_1") (pintype "passive"))
      (node (ref "R19") (pin "1") (pinfunction "1_1") (pintype "passive"))
      (node (ref "R20") (pin "1") (pinfunction "1_1") (pintype "passive"))
      (node (ref "R21") (pin "1") (pinfunction "1_1") (pintype "passive"))
      (node (ref "R22") (pin "1") (pinfunction "1_1") (pintype "passive"))
      (node (ref "R23") (pin "1") (pinfunction "1_1") (pintype "passive"))
      (node (ref "R24") (pin "1") (pinfunction "1_1") (pintype "passive"))
      (node (ref "R25") (pin "1") (pinfunction "1_1") (pintype "passive"))
      (node (ref "R26") (pin "1") (pinfunction "1_1") (pintype "passive"))
      (node (ref "R27") (pin "1") (pinfunction "1_1") (pintype "passive"))
      (node (ref "R28") (pin "1") (pinfunction "1_1") (pintype "passive"))
      (node (ref "R29") (pin "1") (pinfunction "1_1") (pintype "passive"))
      (node (ref "R30") (pin "1") (pinfunction "1_1") (pintype "passive"))
      (node (ref "R33") (pin "2") (pinfunction "2_2") (pintype "passive"))
      (node (ref "R7") (pin "1") (pinfunction "1_1") (pintype "passive"))
      (node (ref "R8") (pin "1") (pinfunction "1_1") (pintype "passive"))
      (node (ref "R9") (pin "1") (pinfunction "1_1") (pintype "passive"))
    )
    (net (code "10") (name "/N$170") (class "Default")
      (node (ref "Q37") (pin "2") (pinfunction "OUT_2") (pintype "output"))
      (node (ref "R100") (pin "1") (pinfunction "1_1") (pintype "passive"))
      (node (ref "R101") (pin "1") (pinfunction "1_1") (pintype "passive"))
      (node (ref "R102") (pin "1") (pinfunction "1_1") (pintype "passive"))
      (node (ref "R103") (pin "1") (pinfunction "1_1") (pintype "passive"))
      (node (ref "R104") (pin "1") (pinfunction "1_1") (pintype "passive"))
      (node (ref "R105") (pin "1") (pinfunction "1_1") (pintype "passive"))
      (node (ref "R106") (pin "1") (pinfunction "1_1") (pintype "passive"))
      (node (ref "R107") (pin "1") (pinfunction "1_1") (pintype "passive"))
      (node (ref "R108") (pin "1") (pinfunction "1_1") (pintype "passive"))
      (node (ref "R109") (pin "1") (pinfunction "1_1") (pintype "passive"))
      (node (ref "R110") (pin "1") (pinfunction "1_1") (pintype "passive"))
      (node (ref "R111") (pin "1") (pinfunction "1_1") (pintype "passive"))
      (node (ref "R112") (pin "1") (pinfunction "1_1") (pintype "passive"))
      (node (ref "R113") (pin "1") (pinfunction "1_1") (pintype "passive"))
      (node (ref "R114") (pin "1") (pinfunction "1_1") (pintype "passive"))
      (node (ref "R115") (pin "1") (pinfunction "1_1") (pintype "passive"))
      (node (ref "R116") (pin "2") (pinfunction "2_2") (pintype "passive"))
      (node (ref "R92") (pin "1") (pinfunction "1_1") (pintype "passive"))
      (node (ref "R93") (pin "1") (pinfunction "1_1") (pintype "passive"))
      (node (ref "R94") (pin "1") (pinfunction "1_1") (pintype "passive"))
      (node (ref "R95") (pin "1") (pinfunction "1_1") (pintype "passive"))
      (node (ref "R96") (pin "1") (pinfunction "1_1") (pintype "passive"))
      (node (ref "R97") (pin "1") (pinfunction "1_1") (pintype "passive"))
    )
    (net (code "11") (name "/N$180") (class "Default")
      (node (ref "Q2") (pin "2") (pinfunction "OUT_2") (pintype "output"))
      (node (ref "R63") (pin "1") (pinfunction "1_1") (pintype "passive"))
      (node (ref "R64") (pin "1") (pinfunction "1_1") (pintype "passive"))
      (node (ref "R65") (pin "1") (pinfunction "1_1") (pintype "passive"))
      (node (ref "R66") (pin "1") (pinfunction "1_1") (pintype "passive"))
      (node (ref "R67") (pin "1") (pinfunction "1_1") (pintype "passive"))
      (node (ref "R68") (pin "1") (pinfunction "1_1") (pintype "passive"))
      (node (ref "R71") (pin "1") (pinfunction "1_1") (pintype "passive"))
      (node (ref "R72") (pin "1") (pinfunction "1_1") (pintype "passive"))
      (node (ref "R73") (pin "1") (pinfunction "1_1") (pintype "passive"))
      (node (ref "R74") (pin "1") (pinfunction "1_1") (pintype "passive"))
      (node (ref "R75") (pin "1") (pinfunction "1_1") (pintype "passive"))
      (node (ref "R76") (pin "1") (pinfunction "1_1") (pintype "passive"))
      (node (ref "R77") (pin "1") (pinfunction "1_1") (pintype "passive"))
      (node (ref "R78") (pin "1") (pinfunction "1_1") (pintype "passive"))
      (node (ref "R79") (pin "1") (pinfunction "1_1") (pintype "passive"))
      (node (ref "R80") (pin "1") (pinfunction "1_1") (pintype "passive"))
      (node (ref "R81") (pin "1") (pinfunction "1_1") (pintype "passive"))
      (node (ref "R82") (pin "1") (pinfunction "1_1") (pintype "passive"))
      (node (ref "R83") (pin "1") (pinfunction "1_1") (pintype "passive"))
      (node (ref "R84") (pin "1") (pinfunction "1_1") (pintype "passive"))
      (node (ref "R85") (pin "1") (pinfunction "1_1") (pintype "passive"))
      (node (ref "R86") (pin "1") (pinfunction "1_1") (pintype "passive"))
      (node (ref "R87") (pin "2") (pinfunction "2_2") (pintype "passive"))
    )
    (net (code "12") (name "/NTC1") (class "Default")
      (node (ref "NTC2") (pin "2") (pinfunction "S_2") (pintype "passive"))
      (node (ref "X2") (pin "6") (pinfunction "KL_6") (pintype "passive"))
    )
    (net (code "13") (name "/OUT1") (class "Default")
      (node (ref "C22") (pin "1") (pinfunction "1_1") (pintype "passive"))
      (node (ref "C4") (pin "2") (pinfunction "2_2") (pintype "passive"))
      (node (ref "C5") (pin "2") (pinfunction "2_2") (pintype "passive"))
      (node (ref "C6") (pin "2") (pinfunction "2_2") (pintype "passive"))
      (node (ref "D49") (pin "A") (pinfunction "A_A") (pintype "passive"))
      (node (ref "D51") (pin "C") (pinfunction "C_C") (pintype "passive"))
      (node (ref "D53") (pin "A") (pinfunction "A_A") (pintype "passive"))
      (node (ref "H1") (pin "B3,2") (pinfunction "MOUNT_B3,2") (pintype "passive"))
      (node (ref "H10") (pin "B3,2") (pinfunction "MOUNT_B3,2") (pintype "passive"))
      (node (ref "H11") (pin "B3,2") (pinfunction "MOUNT_B3,2") (pintype "passive"))
      (node (ref "H2") (pin "B3,2") (pinfunction "MOUNT_B3,2") (pintype "passive"))
      (node (ref "H3") (pin "B3,2") (pinfunction "MOUNT_B3,2") (pintype "passive"))
      (node (ref "Q10") (pin "D") (pinfunction "D_D") (pintype "passive"))
      (node (ref "Q11") (pin "D") (pinfunction "D_D") (pintype "passive"))
      (node (ref "Q12") (pin "D") (pinfunction "D_D") (pintype "passive"))
      (node (ref "Q13") (pin "D") (pinfunction "D_D") (pintype "passive"))
      (node (ref "Q2") (pin "3") (pinfunction "GND_3") (pintype "power_in"))
      (node (ref "Q27") (pin "S") (pinfunction "S_S") (pintype "passive"))
      (node (ref "Q28") (pin "S") (pinfunction "S_S") (pintype "passive"))
      (node (ref "Q29") (pin "S") (pinfunction "S_S") (pintype "passive"))
      (node (ref "Q3") (pin "D") (pinfunction "D_D") (pintype "passive"))
      (node (ref "Q30") (pin "S") (pinfunction "S_S") (pintype "passive"))
      (node (ref "Q31") (pin "S") (pinfunction "S_S") (pintype "passive"))
      (node (ref "Q32") (pin "S") (pinfunction "S_S") (pintype "passive"))
      (node (ref "Q33") (pin "S") (pinfunction "S_S") (pintype "passive"))
      (node (ref "Q34") (pin "S") (pinfunction "S_S") (pintype "passive"))
      (node (ref "Q35") (pin "S") (pinfunction "S_S") (pintype "passive"))
      (node (ref "Q36") (pin "S") (pinfunction "S_S") (pintype "passive"))
      (node (ref "Q4") (pin "D") (pinfunction "D_D") (pintype "passive"))
      (node (ref "Q5") (pin "D") (pinfunction "D_D") (pintype "passive"))
      (node (ref "Q6") (pin "D") (pinfunction "D_D") (pintype "passive"))
      (node (ref "Q7") (pin "D") (pinfunction "D_D") (pintype "passive"))
      (node (ref "Q8") (pin "D") (pinfunction "D_D") (pintype "passive"))
      (node (ref "Q9") (pin "D") (pinfunction "D_D") (pintype "passive"))
      (node (ref "R117") (pin "1") (pinfunction "1_1") (pintype "passive"))
      (node (ref "R3") (pin "2") (pinfunction "2_2") (pintype "passive"))
      (node (ref "R69") (pin "1") (pinfunction "1_1") (pintype "passive"))
      (node (ref "R70") (pin "1") (pinfunction "1_1") (pintype "passive"))
      (node (ref "R87") (pin "1") (pinfunction "1_1") (pintype "passive"))
    )
    (net (code "14") (name "/OUT2") (class "Default")
      (node (ref "C11") (pin "2") (pinfunction "2_2") (pintype "passive"))
      (node (ref "C12") (pin "2") (pinfunction "2_2") (pintype "passive"))
      (node (ref "C13") (pin "2") (pinfunction "2_2") (pintype "passive"))
      (node (ref "C23") (pin "2") (pinfunction "2_2") (pintype "passive"))
      (node (ref "D50") (pin "A") (pinfunction "A_A") (pintype "passive"))
      (node (ref "D52") (pin "C") (pinfunction "C_C") (pintype "passive"))
      (node (ref "D54") (pin "A") (pinfunction "A_A") (pintype "passive"))
      (node (ref "H12") (pin "B3,2") (pinfunction "MOUNT_B3,2") (pintype "passive"))
      (node (ref "H13") (pin "B3,2") (pinfunction "MOUNT_B3,2") (pintype "passive"))
      (node (ref "H14") (pin "B3,2") (pinfunction "MOUNT_B3,2") (pintype "passive"))
      (node (ref "H15") (pin "B3,2") (pinfunction "MOUNT_B3,2") (pintype "passive"))
      (node (ref "H16") (pin "B3,2") (pinfunction "MOUNT_B3,2") (pintype "passive"))
      (node (ref "Q15") (pin "D") (pinfunction "D_D") (pintype "passive"))
      (node (ref "Q16") (pin "D") (pinfunction "D_D") (pintype "passive"))
      (node (ref "Q17") (pin "D") (pinfunction "D_D") (pintype "passive"))
      (node (ref "Q18") (pin "D") (pinfunction "D_D") (pintype "passive"))
      (node (ref "Q19") (pin "D") (pinfunction "D_D") (pintype "passive"))
      (node (ref "Q20") (pin "D") (pinfunction "D_D") (pintype "passive"))
      (node (ref "Q21") (pin "D") (pinfunction "D_D") (pintype "passive"))
      (node (ref "Q22") (pin "D") (pinfunction "D_D") (pintype "passive"))
      (node (ref "Q23") (pin "D") (pinfunction "D_D") (pintype "passive"))
      (node (ref "Q24") (pin "D") (pinfunction "D_D") (pintype "passive"))
      (node (ref "Q25") (pin "D") (pinfunction "D_D") (pintype "passive"))
      (node (ref "Q37") (pin "3") (pinfunction "GND_3") (pintype "power_in"))
      (node (ref "Q39") (pin "S") (pinfunction "S_S") (pintype "passive"))
      (node (ref "Q40") (pin "S") (pinfunction "S_S") (pintype "passive"))
      (node (ref "Q41") (pin "S") (pinfunction "S_S") (pintype "passive"))
      (node (ref "Q42") (pin "S") (pinfunction "S_S") (pintype "passive"))
      (node (ref "Q43") (pin "S") (pinfunction "S_S") (pintype "passive"))
      (node (ref "Q44") (pin "S") (pinfunction "S_S") (pintype "passive"))
      (node (ref "Q45") (pin "S") (pinfunction "S_S") (pintype "passive"))
      (node (ref "Q46") (pin "S") (pinfunction "S_S") (pintype "passive"))
      (node (ref "Q47") (pin "S") (pinfunction "S_S") (pintype "passive"))
      (node (ref "Q48") (pin "S") (pinfunction "S_S") (pintype "passive"))
      (node (ref "R116") (pin "1") (pinfunction "1_1") (pintype "passive"))
      (node (ref "R118") (pin "1") (pinfunction "1_1") (pintype "passive"))
      (node (ref "R88") (pin "2") (pinfunction "2_2") (pintype "passive"))
      (node (ref "R98") (pin "1") (pinfunction "1_1") (pintype "passive"))
      (node (ref "R99") (pin "1") (pinfunction "1_1") (pintype "passive"))
    )
    (net (code "15") (name "GND") (class "Default")
      (node (ref "C17") (pin "-") (pinfunction "-_-") (pintype "passive"))
      (node (ref "C18") (pin "-") (pinfunction "-_-") (pintype "passive"))
      (node (ref "C19") (pin "-") (pinfunction "-_-") (pintype "passive"))
      (node (ref "C20") (pin "-") (pinfunction "-_-") (pintype "passive"))
      (node (ref "C21") (pin "-") (pinfunction "-_-") (pintype "passive"))
      (node (ref "C26") (pin "-") (pinfunction "-_-") (pintype "passive"))
      (node (ref "C27") (pin "-") (pinfunction "-_-") (pintype "passive"))
      (node (ref "C28") (pin "-") (pinfunction "-_-") (pintype "passive"))
      (node (ref "C29") (pin "-") (pinfunction "-_-") (pintype "passive"))
      (node (ref "C30") (pin "-") (pinfunction "-_-") (pintype "passive"))
      (node (ref "C31") (pin "-") (pinfunction "-_-") (pintype "passive"))
      (node (ref "C32") (pin "-") (pinfunction "-_-") (pintype "passive"))
      (node (ref "C33") (pin "-") (pinfunction "-_-") (pintype "passive"))
      (node (ref "C34") (pin "-") (pinfunction "-_-") (pintype "passive"))
      (node (ref "C35") (pin "-") (pinfunction "-_-") (pintype "passive"))
      (node (ref "C36") (pin "-") (pinfunction "-_-") (pintype "passive"))
      (node (ref "CX1") (pin "2") (pinfunction "2_2") (pintype "passive"))
      (node (ref "CX2") (pin "2") (pinfunction "2_2") (pintype "passive"))
      (node (ref "D48") (pin "A") (pinfunction "A_A") (pintype "passive"))
      (node (ref "D51") (pin "A") (pinfunction "A_A") (pintype "passive"))
      (node (ref "D52") (pin "A") (pinfunction "A_A") (pintype "passive"))
      (node (ref "H4") (pin "B4,3") (pinfunction "MOUNT_B4,3") (pintype "passive"))
      (node (ref "H5") (pin "B4,3") (pinfunction "MOUNT_B4,3") (pintype "passive"))
      (node (ref "H6") (pin "B4,3") (pinfunction "MOUNT_B4,3") (pintype "passive"))
      (node (ref "H7") (pin "B4,3") (pinfunction "MOUNT_B4,3") (pintype "passive"))
      (node (ref "H8") (pin "B4,3") (pinfunction "MOUNT_B4,3") (pintype "passive"))
      (node (ref "H9") (pin "B4,3") (pinfunction "MOUNT_B4,3") (pintype "passive"))
      (node (ref "Q1") (pin "3") (pinfunction "GND_3") (pintype "power_in"))
      (node (ref "Q10") (pin "S") (pinfunction "S_S") (pintype "passive"))
      (node (ref "Q11") (pin "S") (pinfunction "S_S") (pintype "passive"))
      (node (ref "Q12") (pin "S") (pinfunction "S_S") (pintype "passive"))
      (node (ref "Q13") (pin "S") (pinfunction "S_S") (pintype "passive"))
      (node (ref "Q14") (pin "3") (pinfunction "GND_3") (pintype "power_in"))
      (node (ref "Q16") (pin "S") (pinfunction "S_S") (pintype "passive"))
      (node (ref "Q17") (pin "S") (pinfunction "S_S") (pintype "passive"))
      (node (ref "Q18") (pin "S") (pinfunction "S_S") (pintype "passive"))
      (node (ref "Q19") (pin "S") (pinfunction "S_S") (pintype "passive"))
      (node (ref "Q20") (pin "S") (pinfunction "S_S") (pintype "passive"))
      (node (ref "Q21") (pin "S") (pinfunction "S_S") (pintype "passive"))
      (node (ref "Q22") (pin "S") (pinfunction "S_S") (pintype "passive"))
      (node (ref "Q23") (pin "S") (pinfunction "S_S") (pintype "passive"))
      (node (ref "Q24") (pin "S") (pinfunction "S_S") (pintype "passive"))
      (node (ref "Q25") (pin "S") (pinfunction "S_S") (pintype "passive"))
      (node (ref "Q4") (pin "S") (pinfunction "S_S") (pintype "passive"))
      (node (ref "Q5") (pin "S") (pinfunction "S_S") (pintype "passive"))
      (node (ref "Q6") (pin "S") (pinfunction "S_S") (pintype "passive"))
      (node (ref "Q7") (pin "S") (pinfunction "S_S") (pintype "passive"))
      (node (ref "Q8") (pin "S") (pinfunction "S_S") (pintype "passive"))
      (node (ref "Q9") (pin "S") (pinfunction "S_S") (pintype "passive"))
      (node (ref "R1") (pin "2") (pinfunction "2_2") (pintype "passive"))
      (node (ref "R119") (pin "1") (pinfunction "1_1") (pintype "passive"))
      (node (ref "R120") (pin "1") (pinfunction "1_1") (pintype "passive"))
      (node (ref "R13") (pin "1") (pinfunction "1_1") (pintype "passive"))
      (node (ref "R14") (pin "1") (pinfunction "1_1") (pintype "passive"))
      (node (ref "R31") (pin "2") (pinfunction "2_2") (pintype "passive"))
      (node (ref "R33") (pin "1") (pinfunction "1_1") (pintype "passive"))
      (node (ref "R42") (pin "1") (pinfunction "1_1") (pintype "passive"))
      (node (ref "R43") (pin "1") (pinfunction "1_1") (pintype "passive"))
      (node (ref "R60") (pin "1") (pinfunction "1_1") (pintype "passive"))
      (node (ref "X2") (pin "3") (pinfunction "KL_3") (pintype "passive"))
      (node (ref "X2") (pin "4") (pinfunction "KL_4") (pintype "passive"))
    )
    (net (code "16") (name "GNDA") (class "Default")
      (node (ref "C14") (pin "2") (pinfunction "2_2") (pintype "passive"))
      (node (ref "C15") (pin "2") (pinfunction "2_2") (pintype "passive"))
      (node (ref "C16") (pin "2") (pinfunction "2_2") (pintype "passive"))
      (node (ref "C7") (pin "2") (pinfunction "2_2") (pintype "passive"))
      (node (ref "C8") (pin "2") (pinfunction "2_2") (pintype "passive"))
      (node (ref "C9") (pin "2") (pinfunction "2_2") (pintype "passive"))
      (node (ref "D47") (pin "A") (pinfunction "A_A") (pintype "passive"))
      (node (ref "U1") (pin "4") (pinfunction "COM_4") (pintype "passive"))
      (node (ref "U2") (pin "4") (pinfunction "COM_4") (pintype "passive"))
      (node (ref "U3") (pin "4") (pinfunction "COM_4") (pintype "passive"))
      (node (ref "U4") (pin "4") (pinfunction "COM_4") (pintype "passive"))
      (node (ref "X2") (pin "13") (pinfunction "KL_13") (pintype "passive"))
      (node (ref "X2") (pin "16") (pinfunction "KL_16") (pintype "passive"))
      (node (ref "X2") (pin "9") (pinfunction "KL_9") (pintype "passive"))
    )
    (net (code "17") (name "Net-(C22-Pad2)") (class "Default")
      (node (ref "C22") (pin "2") (pinfunction "2_2") (pintype "passive"))
      (node (ref "R119") (pin "2") (pinfunction "2_2") (pintype "passive"))
    )
    (net (code "18") (name "Net-(C23-Pad1)") (class "Default")
      (node (ref "C23") (pin "1") (pinfunction "1_1") (pintype "passive"))
      (node (ref "R120") (pin "2") (pinfunction "2_2") (pintype "passive"))
    )
    (net (code "19") (name "Net-(C24-Pad2)") (class "Default")
      (node (ref "C24") (pin "2") (pinfunction "2_2") (pintype "passive"))
      (node (ref "R117") (pin "2") (pinfunction "2_2") (pintype "passive"))
    )
    (net (code "20") (name "Net-(C25-Pad1)") (class "Default")
      (node (ref "C25") (pin "1") (pinfunction "1_1") (pintype "passive"))
      (node (ref "R118") (pin "2") (pinfunction "2_2") (pintype "passive"))
    )
    (net (code "21") (name "Net-(D1-PadA)") (class "Default")
      (node (ref "D1") (pin "A") (pinfunction "A_A") (pintype "passive"))
      (node (ref "Q3") (pin "G") (pinfunction "G_G") (pintype "passive"))
      (node (ref "R7") (pin "2") (pinfunction "2_2") (pintype "passive"))
    )
    (net (code "22") (name "Net-(D1-PadC)") (class "Default")
      (node (ref "D1") (pin "C") (pinfunction "C_C") (pintype "passive"))
      (node (ref "R8") (pin "2") (pinfunction "2_2") (pintype "passive"))
    )
    (net (code "23") (name "Net-(D2-PadA)") (class "Default")
      (node (ref "D2") (pin "A") (pinfunction "A_A") (pintype "passive"))
      (node (ref "Q4") (pin "G") (pinfunction "G_G") (pintype "passive"))
      (node (ref "R9") (pin "2") (pinfunction "2_2") (pintype "passive"))
    )
    (net (code "24") (name "Net-(D2-PadC)") (class "Default")
      (node (ref "D2") (pin "C") (pinfunction "C_C") (pintype "passive"))
      (node (ref "R10") (pin "2") (pinfunction "2_2") (pintype "passive"))
    )
    (net (code "25") (name "Net-(D3-PadA)") (class "Default")
      (node (ref "D3") (pin "A") (pinfunction "A_A") (pintype "passive"))
      (node (ref "Q5") (pin "G") (pinfunction "G_G") (pintype "passive"))
      (node (ref "R11") (pin "2") (pinfunction "2_2") (pintype "passive"))
    )
    (net (code "26") (name "Net-(D3-PadC)") (class "Default")
      (node (ref "D3") (pin "C") (pinfunction "C_C") (pintype "passive"))
      (node (ref "R12") (pin "2") (pinfunction "2_2") (pintype "passive"))
    )
    (net (code "27") (name "Net-(D4-PadA)") (class "Default")
      (node (ref "D4") (pin "A") (pinfunction "A_A") (pintype "passive"))
      (node (ref "Q6") (pin "G") (pinfunction "G_G") (pintype "passive"))
      (node (ref "R15") (pin "2") (pinfunction "2_2") (pintype "passive"))
    )
    (net (code "28") (name "Net-(D4-PadC)") (class "Default")
      (node (ref "D4") (pin "C") (pinfunction "C_C") (pintype "passive"))
      (node (ref "R16") (pin "2") (pinfunction "2_2") (pintype "passive"))
    )
    (net (code "29") (name "Net-(D5-PadA)") (class "Default")
      (node (ref "D5") (pin "A") (pinfunction "A_A") (pintype "passive"))
      (node (ref "Q7") (pin "G") (pinfunction "G_G") (pintype "passive"))
      (node (ref "R17") (pin "2") (pinfunction "2_2") (pintype "passive"))
    )
    (net (code "30") (name "Net-(D5-PadC)") (class "Default")
      (node (ref "D5") (pin "C") (pinfunction "C_C") (pintype "passive"))
      (node (ref "R18") (pin "2") (pinfunction "2_2") (pintype "passive"))
    )
    (net (code "31") (name "Net-(D6-PadA)") (class "Default")
      (node (ref "D6") (pin "A") (pinfunction "A_A") (pintype "passive"))
      (node (ref "Q8") (pin "G") (pinfunction "G_G") (pintype "passive"))
      (node (ref "R19") (pin "2") (pinfunction "2_2") (pintype "passive"))
    )
    (net (code "32") (name "Net-(D6-PadC)") (class "Default")
      (node (ref "D6") (pin "C") (pinfunction "C_C") (pintype "passive"))
      (node (ref "R20") (pin "2") (pinfunction "2_2") (pintype "passive"))
    )
    (net (code "33") (name "Net-(D7-PadA)") (class "Default")
      (node (ref "D7") (pin "A") (pinfunction "A_A") (pintype "passive"))
      (node (ref "Q9") (pin "G") (pinfunction "G_G") (pintype "passive"))
      (node (ref "R21") (pin "2") (pinfunction "2_2") (pintype "passive"))
    )
    (net (code "34") (name "Net-(D7-PadC)") (class "Default")
      (node (ref "D7") (pin "C") (pinfunction "C_C") (pintype "passive"))
      (node (ref "R22") (pin "2") (pinfunction "2_2") (pintype "passive"))
    )
    (net (code "35") (name "Net-(D8-PadA)") (class "Default")
      (node (ref "D8") (pin "A") (pinfunction "A_A") (pintype "passive"))
      (node (ref "Q10") (pin "G") (pinfunction "G_G") (pintype "passive"))
      (node (ref "R23") (pin "2") (pinfunction "2_2") (pintype "passive"))
    )
    (net (code "36") (name "Net-(D8-PadC)") (class "Default")
      (node (ref "D8") (pin "C") (pinfunction "C_C") (pintype "passive"))
      (node (ref "R24") (pin "2") (pinfunction "2_2") (pintype "passive"))
    )
    (net (code "37") (name "Net-(D9-PadA)") (class "Default")
      (node (ref "D9") (pin "A") (pinfunction "A_A") (pintype "passive"))
      (node (ref "Q11") (pin "G") (pinfunction "G_G") (pintype "passive"))
      (node (ref "R25") (pin "2") (pinfunction "2_2") (pintype "passive"))
    )
    (net (code "38") (name "Net-(D9-PadC)") (class "Default")
      (node (ref "D9") (pin "C") (pinfunction "C_C") (pintype "passive"))
      (node (ref "R26") (pin "2") (pinfunction "2_2") (pintype "passive"))
    )
    (net (code "39") (name "Net-(D10-PadA)") (class "Default")
      (node (ref "D10") (pin "A") (pinfunction "A_A") (pintype "passive"))
      (node (ref "Q12") (pin "G") (pinfunction "G_G") (pintype "passive"))
      (node (ref "R27") (pin "2") (pinfunction "2_2") (pintype "passive"))
    )
    (net (code "40") (name "Net-(D10-PadC)") (class "Default")
      (node (ref "D10") (pin "C") (pinfunction "C_C") (pintype "passive"))
      (node (ref "R28") (pin "2") (pinfunction "2_2") (pintype "passive"))
    )
    (net (code "41") (name "Net-(D11-PadA)") (class "Default")
      (node (ref "D11") (pin "A") (pinfunction "A_A") (pintype "passive"))
      (node (ref "Q13") (pin "G") (pinfunction "G_G") (pintype "passive"))
      (node (ref "R29") (pin "2") (pinfunction "2_2") (pintype "passive"))
    )
    (net (code "42") (name "Net-(D11-PadC)") (class "Default")
      (node (ref "D11") (pin "C") (pinfunction "C_C") (pintype "passive"))
      (node (ref "R30") (pin "2") (pinfunction "2_2") (pintype "passive"))
    )
    (net (code "43") (name "Net-(D12-PadA)") (class "Default")
      (node (ref "D12") (pin "A") (pinfunction "A_A") (pintype "passive"))
      (node (ref "Q15") (pin "G") (pinfunction "G_G") (pintype "passive"))
      (node (ref "R36") (pin "2") (pinfunction "2_2") (pintype "passive"))
    )
    (net (code "44") (name "Net-(D12-PadC)") (class "Default")
      (node (ref "D12") (pin "C") (pinfunction "C_C") (pintype "passive"))
      (node (ref "R37") (pin "2") (pinfunction "2_2") (pintype "passive"))
    )
    (net (code "45") (name "Net-(D13-PadA)") (class "Default")
      (node (ref "D13") (pin "A") (pinfunction "A_A") (pintype "passive"))
      (node (ref "Q16") (pin "G") (pinfunction "G_G") (pintype "passive"))
      (node (ref "R38") (pin "2") (pinfunction "2_2") (pintype "passive"))
    )
    (net (code "46") (name "Net-(D13-PadC)") (class "Default")
      (node (ref "D13") (pin "C") (pinfunction "C_C") (pintype "passive"))
      (node (ref "R39") (pin "2") (pinfunction "2_2") (pintype "passive"))
    )
    (net (code "47") (name "Net-(D14-PadA)") (class "Default")
      (node (ref "D14") (pin "A") (pinfunction "A_A") (pintype "passive"))
      (node (ref "Q17") (pin "G") (pinfunction "G_G") (pintype "passive"))
      (node (ref "R40") (pin "2") (pinfunction "2_2") (pintype "passive"))
    )
    (net (code "48") (name "Net-(D14-PadC)") (class "Default")
      (node (ref "D14") (pin "C") (pinfunction "C_C") (pintype "passive"))
      (node (ref "R41") (pin "2") (pinfunction "2_2") (pintype "passive"))
    )
    (net (code "49") (name "Net-(D15-PadA)") (class "Default")
      (node (ref "D15") (pin "A") (pinfunction "A_A") (pintype "passive"))
      (node (ref "Q18") (pin "G") (pinfunction "G_G") (pintype "passive"))
      (node (ref "R44") (pin "2") (pinfunction "2_2") (pintype "passive"))
    )
    (net (code "50") (name "Net-(D15-PadC)") (class "Default")
      (node (ref "D15") (pin "C") (pinfunction "C_C") (pintype "passive"))
      (node (ref "R45") (pin "2") (pinfunction "2_2") (pintype "passive"))
    )
    (net (code "51") (name "Net-(D16-PadA)") (class "Default")
      (node (ref "D16") (pin "A") (pinfunction "A_A") (pintype "passive"))
      (node (ref "Q19") (pin "G") (pinfunction "G_G") (pintype "passive"))
      (node (ref "R46") (pin "2") (pinfunction "2_2") (pintype "passive"))
    )
    (net (code "52") (name "Net-(D16-PadC)") (class "Default")
      (node (ref "D16") (pin "C") (pinfunction "C_C") (pintype "passive"))
      (node (ref "R47") (pin "2") (pinfunction "2_2") (pintype "passive"))
    )
    (net (code "53") (name "Net-(D17-PadA)") (class "Default")
      (node (ref "D17") (pin "A") (pinfunction "A_A") (pintype "passive"))
      (node (ref "Q20") (pin "G") (pinfunction "G_G") (pintype "passive"))
      (node (ref "R48") (pin "2") (pinfunction "2_2") (pintype "passive"))
    )
    (net (code "54") (name "Net-(D17-PadC)") (class "Default")
      (node (ref "D17") (pin "C") (pinfunction "C_C") (pintype "passive"))
      (node (ref "R49") (pin "2") (pinfunction "2_2") (pintype "passive"))
    )
    (net (code "55") (name "Net-(D18-PadA)") (class "Default")
      (node (ref "D18") (pin "A") (pinfunction "A_A") (pintype "passive"))
      (node (ref "Q21") (pin "G") (pinfunction "G_G") (pintype "passive"))
      (node (ref "R50") (pin "2") (pinfunction "2_2") (pintype "passive"))
    )
    (net (code "56") (name "Net-(D18-PadC)") (class "Default")
      (node (ref "D18") (pin "C") (pinfunction "C_C") (pintype "passive"))
      (node (ref "R51") (pin "2") (pinfunction "2_2") (pintype "passive"))
    )
    (net (code "57") (name "Net-(D19-PadA)") (class "Default")
      (node (ref "D19") (pin "A") (pinfunction "A_A") (pintype "passive"))
      (node (ref "Q22") (pin "G") (pinfunction "G_G") (pintype "passive"))
      (node (ref "R52") (pin "2") (pinfunction "2_2") (pintype "passive"))
    )
    (net (code "58") (name "Net-(D19-PadC)") (class "Default")
      (node (ref "D19") (pin "C") (pinfunction "C_C") (pintype "passive"))
      (node (ref "R53") (pin "2") (pinfunction "2_2") (pintype "passive"))
    )
    (net (code "59") (name "Net-(D20-PadA)") (class "Default")
      (node (ref "D20") (pin "A") (pinfunction "A_A") (pintype "passive"))
      (node (ref "Q23") (pin "G") (pinfunction "G_G") (pintype "passive"))
      (node (ref "R54") (pin "2") (pinfunction "2_2") (pintype "passive"))
    )
    (net (code "60") (name "Net-(D20-PadC)") (class "Default")
      (node (ref "D20") (pin "C") (pinfunction "C_C") (pintype "passive"))
      (node (ref "R55") (pin "2") (pinfunction "2_2") (pintype "passive"))
    )
    (net (code "61") (name "Net-(D21-PadA)") (class "Default")
      (node (ref "D21") (pin "A") (pinfunction "A_A") (pintype "passive"))
      (node (ref "Q24") (pin "G") (pinfunction "G_G") (pintype "passive"))
      (node (ref "R56") (pin "2") (pinfunction "2_2") (pintype "passive"))
    )
    (net (code "62") (name "Net-(D21-PadC)") (class "Default")
      (node (ref "D21") (pin "C") (pinfunction "C_C") (pintype "passive"))
      (node (ref "R57") (pin "2") (pinfunction "2_2") (pintype "passive"))
    )
    (net (code "63") (name "Net-(D22-PadA)") (class "Default")
      (node (ref "D22") (pin "A") (pinfunction "A_A") (pintype "passive"))
      (node (ref "Q25") (pin "G") (pinfunction "G_G") (pintype "passive"))
      (node (ref "R58") (pin "2") (pinfunction "2_2") (pintype "passive"))
    )
    (net (code "64") (name "Net-(D22-PadC)") (class "Default")
      (node (ref "D22") (pin "C") (pinfunction "C_C") (pintype "passive"))
      (node (ref "R59") (pin "2") (pinfunction "2_2") (pintype "passive"))
    )
    (net (code "65") (name "Net-(D23-PadA)") (class "Default")
      (node (ref "D23") (pin "A") (pinfunction "A_A") (pintype "passive"))
      (node (ref "Q26") (pin "G") (pinfunction "G_G") (pintype "passive"))
      (node (ref "R63") (pin "2") (pinfunction "2_2") (pintype "passive"))
    )
    (net (code "66") (name "Net-(D23-PadC)") (class "Default")
      (node (ref "D23") (pin "C") (pinfunction "C_C") (pintype "passive"))
      (node (ref "R64") (pin "2") (pinfunction "2_2") (pintype "passive"))
    )
    (net (code "67") (name "Net-(D24-PadA)") (class "Default")
      (node (ref "D24") (pin "A") (pinfunction "A_A") (pintype "passive"))
      (node (ref "Q27") (pin "G") (pinfunction "G_G") (pintype "passive"))
      (node (ref "R65") (pin "2") (pinfunction "2_2") (pintype "passive"))
    )
    (net (code "68") (name "Net-(D24-PadC)") (class "Default")
      (node (ref "D24") (pin "C") (pinfunction "C_C") (pintype "passive"))
      (node (ref "R66") (pin "2") (pinfunction "2_2") (pintype "passive"))
    )
    (net (code "69") (name "Net-(D25-PadA)") (class "Default")
      (node (ref "D25") (pin "A") (pinfunction "A_A") (pintype "passive"))
      (node (ref "Q28") (pin "G") (pinfunction "G_G") (pintype "passive"))
      (node (ref "R67") (pin "2") (pinfunction "2_2") (pintype "passive"))
    )
    (net (code "70") (name "Net-(D25-PadC)") (class "Default")
      (node (ref "D25") (pin "C") (pinfunction "C_C") (pintype "passive"))
      (node (ref "R68") (pin "2") (pinfunction "2_2") (pintype "passive"))
    )
    (net (code "71") (name "Net-(D26-PadA)") (class "Default")
      (node (ref "D26") (pin "A") (pinfunction "A_A") (pintype "passive"))
      (node (ref "Q29") (pin "G") (pinfunction "G_G") (pintype "passive"))
      (node (ref "R71") (pin "2") (pinfunction "2_2") (pintype "passive"))
    )
    (net (code "72") (name "Net-(D26-PadC)") (class "Default")
      (node (ref "D26") (pin "C") (pinfunction "C_C") (pintype "passive"))
      (node (ref "R72") (pin "2") (pinfunction "2_2") (pintype "passive"))
    )
    (net (code "73") (name "Net-(D27-PadA)") (class "Default")
      (node (ref "D27") (pin "A") (pinfunction "A_A") (pintype "passive"))
      (node (ref "Q30") (pin "G") (pinfunction "G_G") (pintype "passive"))
      (node (ref "R73") (pin "2") (pinfunction "2_2") (pintype "passive"))
    )
    (net (code "74") (name "Net-(D27-PadC)") (class "Default")
      (node (ref "D27") (pin "C") (pinfunction "C_C") (pintype "passive"))
      (node (ref "R74") (pin "2") (pinfunction "2_2") (pintype "passive"))
    )
    (net (code "75") (name "Net-(D28-PadA)") (class "Default")
      (node (ref "D28") (pin "A") (pinfunction "A_A") (pintype "passive"))
      (node (ref "Q31") (pin "G") (pinfunction "G_G") (pintype "passive"))
      (node (ref "R75") (pin "2") (pinfunction "2_2") (pintype "passive"))
    )
    (net (code "76") (name "Net-(D28-PadC)") (class "Default")
      (node (ref "D28") (pin "C") (pinfunction "C_C") (pintype "passive"))
      (node (ref "R76") (pin "2") (pinfunction "2_2") (pintype "passive"))
    )
    (net (code "77") (name "Net-(D29-PadA)") (class "Default")
      (node (ref "D29") (pin "A") (pinfunction "A_A") (pintype "passive"))
      (node (ref "Q32") (pin "G") (pinfunction "G_G") (pintype "passive"))
      (node (ref "R77") (pin "2") (pinfunction "2_2") (pintype "passive"))
    )
    (net (code "78") (name "Net-(D29-PadC)") (class "Default")
      (node (ref "D29") (pin "C") (pinfunction "C_C") (pintype "passive"))
      (node (ref "R78") (pin "2") (pinfunction "2_2") (pintype "passive"))
    )
    (net (code "79") (name "Net-(D30-PadA)") (class "Default")
      (node (ref "D30") (pin "A") (pinfunction "A_A") (pintype "passive"))
      (node (ref "Q33") (pin "G") (pinfunction "G_G") (pintype "passive"))
      (node (ref "R79") (pin "2") (pinfunction "2_2") (pintype "passive"))
    )
    (net (code "80") (name "Net-(D30-PadC)") (class "Default")
      (node (ref "D30") (pin "C") (pinfunction "C_C") (pintype "passive"))
      (node (ref "R80") (pin "2") (pinfunction "2_2") (pintype "passive"))
    )
    (net (code "81") (name "Net-(D31-PadA)") (class "Default")
      (node (ref "D31") (pin "A") (pinfunction "A_A") (pintype "passive"))
      (node (ref "Q34") (pin "G") (pinfunction "G_G") (pintype "passive"))
      (node (ref "R81") (pin "2") (pinfunction "2_2") (pintype "passive"))
    )
    (net (code "82") (name "Net-(D31-PadC)") (class "Default")
      (node (ref "D31") (pin "C") (pinfunction "C_C") (pintype "passive"))
      (node (ref "R82") (pin "2") (pinfunction "2_2") (pintype "passive"))
    )
    (net (code "83") (name "Net-(D32-PadA)") (class "Default")
      (node (ref "D32") (pin "A") (pinfunction "A_A") (pintype "passive"))
      (node (ref "Q35") (pin "G") (pinfunction "G_G") (pintype "passive"))
      (node (ref "R83") (pin "2") (pinfunction "2_2") (pintype "passive"))
    )
    (net (code "84") (name "Net-(D32-PadC)") (class "Default")
      (node (ref "D32") (pin "C") (pinfunction "C_C") (pintype "passive"))
      (node (ref "R84") (pin "2") (pinfunction "2_2") (pintype "passive"))
    )
    (net (code "85") (name "Net-(D33-PadA)") (class "Default")
      (node (ref "D33") (pin "A") (pinfunction "A_A") (pintype "passive"))
      (node (ref "Q36") (pin "G") (pinfunction "G_G") (pintype "passive"))
      (node (ref "R85") (pin "2") (pinfunction "2_2") (pintype "passive"))
    )
    (net (code "86") (name "Net-(D33-PadC)") (class "Default")
      (node (ref "D33") (pin "C") (pinfunction "C_C") (pintype "passive"))
      (node (ref "R86") (pin "2") (pinfunction "2_2") (pintype "passive"))
    )
    (net (code "87") (name "Net-(D35-PadA)") (class "Default")
      (node (ref "D35") (pin "A") (pinfunction "A_A") (pintype "passive"))
      (node (ref "Q38") (pin "G") (pinfunction "G_G") (pintype "passive"))
      (node (ref "R92") (pin "2") (pinfunction "2_2") (pintype "passive"))
    )
    (net (code "88") (name "Net-(D35-PadC)") (class "Default")
      (node (ref "D35") (pin "C") (pinfunction "C_C") (pintype "passive"))
      (node (ref "R93") (pin "2") (pinfunction "2_2") (pintype "passive"))
    )
    (net (code "89") (name "Net-(D36-PadA)") (class "Default")
      (node (ref "D36") (pin "A") (pinfunction "A_A") (pintype "passive"))
      (node (ref "Q39") (pin "G") (pinfunction "G_G") (pintype "passive"))
      (node (ref "R94") (pin "2") (pinfunction "2_2") (pintype "passive"))
    )
    (net (code "90") (name "Net-(D36-PadC)") (class "Default")
      (node (ref "D36") (pin "C") (pinfunction "C_C") (pintype "passive"))
      (node (ref "R95") (pin "2") (pinfunction "2_2") (pintype "passive"))
    )
    (net (code "91") (name "Net-(D37-PadA)") (class "Default")
      (node (ref "D37") (pin "A") (pinfunction "A_A") (pintype "passive"))
      (node (ref "Q40") (pin "G") (pinfunction "G_G") (pintype "passive"))
      (node (ref "R96") (pin "2") (pinfunction "2_2") (pintype "passive"))
    )
    (net (code "92") (name "Net-(D37-PadC)") (class "Default")
      (node (ref "D37") (pin "C") (pinfunction "C_C") (pintype "passive"))
      (node (ref "R97") (pin "2") (pinfunction "2_2") (pintype "passive"))
    )
    (net (code "93") (name "Net-(D38-PadA)") (class "Default")
      (node (ref "D38") (pin "A") (pinfunction "A_A") (pintype "passive"))
      (node (ref "Q41") (pin "G") (pinfunction "G_G") (pintype "passive"))
      (node (ref "R100") (pin "2") (pinfunction "2_2") (pintype "passive"))
    )
    (net (code "94") (name "Net-(D38-PadC)") (class "Default")
      (node (ref "D38") (pin "C") (pinfunction "C_C") (pintype "passive"))
      (node (ref "R101") (pin "2") (pinfunction "2_2") (pintype "passive"))
    )
    (net (code "95") (name "Net-(D39-PadA)") (class "Default")
      (node (ref "D39") (pin "A") (pinfunction "A_A") (pintype "passive"))
      (node (ref "Q42") (pin "G") (pinfunction "G_G") (pintype "passive"))
      (node (ref "R102") (pin "2") (pinfunction "2_2") (pintype "passive"))
    )
    (net (code "96") (name "Net-(D39-PadC)") (class "Default")
      (node (ref "D39") (pin "C") (pinfunction "C_C") (pintype "passive"))
      (node (ref "R103") (pin "2") (pinfunction "2_2") (pintype "passive"))
    )
    (net (code "97") (name "Net-(D40-PadA)") (class "Default")
      (node (ref "D40") (pin "A") (pinfunction "A_A") (pintype "passive"))
      (node (ref "Q43") (pin "G") (pinfunction "G_G") (pintype "passive"))
      (node (ref "R104") (pin "2") (pinfunction "2_2") (pintype "passive"))
    )
    (net (code "98") (name "Net-(D40-PadC)") (class "Default")
      (node (ref "D40") (pin "C") (pinfunction "C_C") (pintype "passive"))
      (node (ref "R105") (pin "2") (pinfunction "2_2") (pintype "passive"))
    )
    (net (code "99") (name "Net-(D41-PadA)") (class "Default")
      (node (ref "D41") (pin "A") (pinfunction "A_A") (pintype "passive"))
      (node (ref "Q44") (pin "G") (pinfunction "G_G") (pintype "passive"))
      (node (ref "R106") (pin "2") (pinfunction "2_2") (pintype "passive"))
    )
    (net (code "100") (name "Net-(D41-PadC)") (class "Default")
      (node (ref "D41") (pin "C") (pinfunction "C_C") (pintype "passive"))
      (node (ref "R107") (pin "2") (pinfunction "2_2") (pintype "passive"))
    )
    (net (code "101") (name "Net-(D42-PadA)") (class "Default")
      (node (ref "D42") (pin "A") (pinfunction "A_A") (pintype "passive"))
      (node (ref "Q45") (pin "G") (pinfunction "G_G") (pintype "passive"))
      (node (ref "R108") (pin "2") (pinfunction "2_2") (pintype "passive"))
    )
    (net (code "102") (name "Net-(D42-PadC)") (class "Default")
      (node (ref "D42") (pin "C") (pinfunction "C_C") (pintype "passive"))
      (node (ref "R109") (pin "2") (pinfunction "2_2") (pintype "passive"))
    )
    (net (code "103") (name "Net-(D43-PadA)") (class "Default")
      (node (ref "D43") (pin "A") (pinfunction "A_A") (pintype "passive"))
      (node (ref "Q46") (pin "G") (pinfunction "G_G") (pintype "passive"))
      (node (ref "R110") (pin "2") (pinfunction "2_2") (pintype "passive"))
    )
    (net (code "104") (name "Net-(D43-PadC)") (class "Default")
      (node (ref "D43") (pin "C") (pinfunction "C_C") (pintype "passive"))
      (node (ref "R111") (pin "2") (pinfunction "2_2") (pintype "passive"))
    )
    (net (code "105") (name "Net-(D44-PadA)") (class "Default")
      (node (ref "D44") (pin "A") (pinfunction "A_A") (pintype "passive"))
      (node (ref "Q47") (pin "G") (pinfunction "G_G") (pintype "passive"))
      (node (ref "R112") (pin "2") (pinfunction "2_2") (pintype "passive"))
    )
    (net (code "106") (name "Net-(D44-PadC)") (class "Default")
      (node (ref "D44") (pin "C") (pinfunction "C_C") (pintype "passive"))
      (node (ref "R113") (pin "2") (pinfunction "2_2") (pintype "passive"))
    )
    (net (code "107") (name "Net-(D45-PadA)") (class "Default")
      (node (ref "D45") (pin "A") (pinfunction "A_A") (pintype "passive"))
      (node (ref "Q48") (pin "G") (pinfunction "G_G") (pintype "passive"))
      (node (ref "R114") (pin "2") (pinfunction "2_2") (pintype "passive"))
    )
    (net (code "108") (name "Net-(D45-PadC)") (class "Default")
      (node (ref "D45") (pin "C") (pinfunction "C_C") (pintype "passive"))
      (node (ref "R115") (pin "2") (pinfunction "2_2") (pintype "passive"))
    )
    (net (code "109") (name "Net-(Q1-IN)") (class "Default")
      (node (ref "Q1") (pin "4") (pinfunction "IN_4") (pintype "input"))
      (node (ref "R2") (pin "2") (pinfunction "2_2") (pintype "passive"))
    )
    (net (code "110") (name "Net-(Q2-IN)") (class "Default")
      (node (ref "Q2") (pin "4") (pinfunction "IN_4") (pintype "input"))
      (node (ref "R4") (pin "2") (pinfunction "2_2") (pintype "passive"))
    )
    (net (code "111") (name "Net-(Q2-VCC)") (class "Default")
      (node (ref "C4") (pin "1") (pinfunction "1_1") (pintype "passive"))
      (node (ref "C5") (pin "1") (pinfunction "1_1") (pintype "passive"))
      (node (ref "C6") (pin "1") (pinfunction "1_1") (pintype "passive"))
      (node (ref "D34") (pin "C") (pinfunction "C_C") (pintype "passive"))
      (node (ref "D49") (pin "C") (pinfunction "C_C") (pintype "passive"))
      (node (ref "Q2") (pin "1") (pinfunction "VCC_1") (pintype "power_in"))
      (node (ref "U2") (pin "8") (pinfunction "VB_8") (pintype "power_in"))
    )
    (net (code "112") (name "Net-(Q3-PadS)") (class "Default")
      (node (ref "Q3") (pin "S") (pinfunction "S_S") (pintype "passive"))
      (node (ref "R13") (pin "2") (pinfunction "2_2") (pintype "passive"))
      (node (ref "R14") (pin "2") (pinfunction "2_2") (pintype "passive"))
      (node (ref "R6") (pin "2") (pinfunction "2_2") (pintype "passive"))
    )
    (net (code "113") (name "Net-(Q14-IN)") (class "Default")
      (node (ref "Q14") (pin "4") (pinfunction "IN_4") (pintype "input"))
      (node (ref "R32") (pin "2") (pinfunction "2_2") (pintype "passive"))
    )
    (net (code "114") (name "Net-(Q15-PadS)") (class "Default")
      (node (ref "Q15") (pin "S") (pinfunction "S_S") (pintype "passive"))
      (node (ref "R35") (pin "2") (pinfunction "2_2") (pintype "passive"))
      (node (ref "R42") (pin "2") (pinfunction "2_2") (pintype "passive"))
      (node (ref "R43") (pin "2") (pinfunction "2_2") (pintype "passive"))
    )
    (net (code "115") (name "Net-(Q26-PadS)") (class "Default")
      (node (ref "Q26") (pin "S") (pinfunction "S_S") (pintype "passive"))
      (node (ref "R62") (pin "2") (pinfunction "2_2") (pintype "passive"))
      (node (ref "R69") (pin "2") (pinfunction "2_2") (pintype "passive"))
      (node (ref "R70") (pin "2") (pinfunction "2_2") (pintype "passive"))
    )
    (net (code "116") (name "Net-(Q37-IN)") (class "Default")
      (node (ref "Q37") (pin "4") (pinfunction "IN_4") (pintype "input"))
      (node (ref "R89") (pin "2") (pinfunction "2_2") (pintype "passive"))
    )
    (net (code "117") (name "Net-(Q37-VCC)") (class "Default")
      (node (ref "C11") (pin "1") (pinfunction "1_1") (pintype "passive"))
      (node (ref "C12") (pin "1") (pinfunction "1_1") (pintype "passive"))
      (node (ref "C13") (pin "1") (pinfunction "1_1") (pintype "passive"))
      (node (ref "D46") (pin "C") (pinfunction "C_C") (pintype "passive"))
      (node (ref "D50") (pin "C") (pinfunction "C_C") (pintype "passive"))
      (node (ref "Q37") (pin "1") (pinfunction "VCC_1") (pintype "power_in"))
      (node (ref "U4") (pin "8") (pinfunction "VB_8") (pintype "power_in"))
    )
    (net (code "118") (name "Net-(U1-CS)") (class "Default")
      (node (ref "C1") (pin "1") (pinfunction "1_1") (pintype "passive"))
      (node (ref "R5") (pin "1") (pinfunction "1_1") (pintype "passive"))
      (node (ref "R6") (pin "1") (pinfunction "1_1") (pintype "passive"))
      (node (ref "U1") (pin "6") (pinfunction "CS_6") (pintype "input"))
    )
    (net (code "119") (name "Net-(U1-HO)") (class "Default")
      (node (ref "R2") (pin "1") (pinfunction "1_1") (pintype "passive"))
      (node (ref "U1") (pin "7") (pinfunction "HO_7") (pintype "output"))
    )
    (net (code "120") (name "Net-(U1-VS)") (class "Default")
      (node (ref "C1") (pin "2") (pinfunction "2_2") (pintype "passive"))
      (node (ref "R1") (pin "1") (pinfunction "1_1") (pintype "passive"))
      (node (ref "R5") (pin "2") (pinfunction "2_2") (pintype "passive"))
      (node (ref "U1") (pin "5") (pinfunction "VS_5") (pintype "power_in"))
    )
    (net (code "121") (name "Net-(U2-CS)") (class "Default")
      (node (ref "C3") (pin "1") (pinfunction "1_1") (pintype "passive"))
      (node (ref "R61") (pin "1") (pinfunction "1_1") (pintype "passive"))
      (node (ref "R62") (pin "1") (pinfunction "1_1") (pintype "passive"))
      (node (ref "U2") (pin "6") (pinfunction "CS_6") (pintype "input"))
    )
    (net (code "122") (name "Net-(U2-HO)") (class "Default")
      (node (ref "R4") (pin "1") (pinfunction "1_1") (pintype "passive"))
      (node (ref "U2") (pin "7") (pinfunction "HO_7") (pintype "output"))
    )
    (net (code "123") (name "Net-(U2-VS)") (class "Default")
      (node (ref "C3") (pin "2") (pinfunction "2_2") (pintype "passive"))
      (node (ref "R3") (pin "1") (pinfunction "1_1") (pintype "passive"))
      (node (ref "R61") (pin "2") (pinfunction "2_2") (pintype "passive"))
      (node (ref "U2") (pin "5") (pinfunction "VS_5") (pintype "power_in"))
    )
    (net (code "124") (name "Net-(U3-CS)") (class "Default")
      (node (ref "C2") (pin "1") (pinfunction "1_1") (pintype "passive"))
      (node (ref "R34") (pin "1") (pinfunction "1_1") (pintype "passive"))
      (node (ref "R35") (pin "1") (pinfunction "1_1") (pintype "passive"))
      (node (ref "U3") (pin "6") (pinfunction "CS_6") (pintype "input"))
    )
    (net (code "125") (name "Net-(U3-HO)") (class "Default")
      (node (ref "R32") (pin "1") (pinfunction "1_1") (pintype "passive"))
      (node (ref "U3") (pin "7") (pinfunction "HO_7") (pintype "output"))
    )
    (net (code "126") (name "Net-(U3-VS)") (class "Default")
      (node (ref "C2") (pin "2") (pinfunction "2_2") (pintype "passive"))
      (node (ref "R31") (pin "1") (pinfunction "1_1") (pintype "passive"))
      (node (ref "R34") (pin "2") (pinfunction "2_2") (pintype "passive"))
      (node (ref "U3") (pin "5") (pinfunction "VS_5") (pintype "power_in"))
    )
    (net (code "127") (name "Net-(U4-CS)") (class "Default")
      (node (ref "C10") (pin "1") (pinfunction "1_1") (pintype "passive"))
      (node (ref "R90") (pin "1") (pinfunction "1_1") (pintype "passive"))
      (node (ref "R91") (pin "1") (pinfunction "1_1") (pintype "passive"))
      (node (ref "U4") (pin "6") (pinfunction "CS_6") (pintype "input"))
    )
    (net (code "128") (name "Net-(U4-HO)") (class "Default")
      (node (ref "R89") (pin "1") (pinfunction "1_1") (pintype "passive"))
      (node (ref "U4") (pin "7") (pinfunction "HO_7") (pintype "output"))
    )
    (net (code "129") (name "Net-(U4-VS)") (class "Default")
      (node (ref "C10") (pin "2") (pinfunction "2_2") (pintype "passive"))
      (node (ref "R88") (pin "1") (pinfunction "1_1") (pintype "passive"))
      (node (ref "R90") (pin "2") (pinfunction "2_2") (pintype "passive"))
      (node (ref "U4") (pin "5") (pinfunction "VS_5") (pintype "power_in"))
    )
    (net (code "130") (name "VCC") (class "Default")
      (node (ref "C14") (pin "1") (pinfunction "1_1") (pintype "passive"))
      (node (ref "C15") (pin "1") (pinfunction "1_1") (pintype "passive"))
      (node (ref "C16") (pin "1") (pinfunction "1_1") (pintype "passive"))
      (node (ref "C7") (pin "1") (pinfunction "1_1") (pintype "passive"))
      (node (ref "C8") (pin "1") (pinfunction "1_1") (pintype "passive"))
      (node (ref "C9") (pin "1") (pinfunction "1_1") (pintype "passive"))
      (node (ref "D34") (pin "A") (pinfunction "A_A") (pintype "passive"))
      (node (ref "D46") (pin "A") (pinfunction "A_A") (pintype "passive"))
      (node (ref "D47") (pin "C") (pinfunction "C_C") (pintype "passive"))
      (node (ref "Q1") (pin "1") (pinfunction "VCC_1") (pintype "power_in"))
      (node (ref "Q14") (pin "1") (pinfunction "VCC_1") (pintype "power_in"))
      (node (ref "U1") (pin "1") (pinfunction "VCC_1") (pintype "power_in"))
      (node (ref "U1") (pin "8") (pinfunction "VB_8") (pintype "power_in"))
      (node (ref "U2") (pin "1") (pinfunction "VCC_1") (pintype "power_in"))
      (node (ref "U3") (pin "1") (pinfunction "VCC_1") (pintype "power_in"))
      (node (ref "U3") (pin "8") (pinfunction "VB_8") (pintype "power_in"))
      (node (ref "U4") (pin "1") (pinfunction "VCC_1") (pintype "power_in"))
      (node (ref "X2") (pin "7") (pinfunction "KL_7") (pintype "passive"))
      (node (ref "X2") (pin "8") (pinfunction "KL_8") (pintype "passive"))
    )
    (net (code "131") (name "VCC{slash}2") (class "Default")
      (node (ref "C17") (pin "+") (pinfunction "+_+") (pintype "passive"))
      (node (ref "C18") (pin "+") (pinfunction "+_+") (pintype "passive"))
      (node (ref "C19") (pin "+") (pinfunction "+_+") (pintype "passive"))
      (node (ref "C20") (pin "+") (pinfunction "+_+") (pintype "passive"))
      (node (ref "C21") (pin "+") (pinfunction "+_+") (pintype "passive"))
      (node (ref "C24") (pin "1") (pinfunction "1_1") (pintype "passive"))
      (node (ref "C25") (pin "2") (pinfunction "2_2") (pintype "passive"))
      (node (ref "C26") (pin "+") (pinfunction "+_+") (pintype "passive"))
      (node (ref "C27") (pin "+") (pinfunction "+_+") (pintype "passive"))
      (node (ref "C28") (pin "+") (pinfunction "+_+") (pintype "passive"))
      (node (ref "C29") (pin "+") (pinfunction "+_+") (pintype "passive"))
      (node (ref "C30") (pin "+") (pinfunction "+_+") (pintype "passive"))
      (node (ref "C31") (pin "+") (pinfunction "+_+") (pintype "passive"))
      (node (ref "C32") (pin "+") (pinfunction "+_+") (pintype "passive"))
      (node (ref "C33") (pin "+") (pinfunction "+_+") (pintype "passive"))
      (node (ref "C34") (pin "+") (pinfunction "+_+") (pintype "passive"))
      (node (ref "C35") (pin "+") (pinfunction "+_+") (pintype "passive"))
      (node (ref "C36") (pin "+") (pinfunction "+_+") (pintype "passive"))
      (node (ref "CX1") (pin "1") (pinfunction "1_1") (pintype "passive"))
      (node (ref "CX2") (pin "1") (pinfunction "1_1") (pintype "passive"))
      (node (ref "D48") (pin "C") (pinfunction "C_C") (pintype "passive"))
      (node (ref "D53") (pin "C") (pinfunction "C_C") (pintype "passive"))
      (node (ref "D54") (pin "C") (pinfunction "C_C") (pintype "passive"))
      (node (ref "H17") (pin "B3,2") (pinfunction "MOUNT_B3,2") (pintype "passive"))
      (node (ref "H18") (pin "B3,2") (pinfunction "MOUNT_B3,2") (pintype "passive"))
      (node (ref "H19") (pin "B3,2") (pinfunction "MOUNT_B3,2") (pintype "passive"))
      (node (ref "H20") (pin "B3,2") (pinfunction "MOUNT_B3,2") (pintype "passive"))
      (node (ref "H21") (pin "B3,2") (pinfunction "MOUNT_B3,2") (pintype "passive"))
      (node (ref "H22") (pin "B3,2") (pinfunction "MOUNT_B3,2") (pintype "passive"))
      (node (ref "H23") (pin "B3,2") (pinfunction "MOUNT_B3,2") (pintype "passive"))
      (node (ref "H24") (pin "B3,2") (pinfunction "MOUNT_B3,2") (pintype "passive"))
      (node (ref "H26") (pin "B3,2") (pinfunction "MOUNT_B3,2") (pintype "passive"))
      (node (ref "Q26") (pin "D") (pinfunction "D_D") (pintype "passive"))
      (node (ref "Q27") (pin "D") (pinfunction "D_D") (pintype "passive"))
      (node (ref "Q28") (pin "D") (pinfunction "D_D") (pintype "passive"))
      (node (ref "Q29") (pin "D") (pinfunction "D_D") (pintype "passive"))
      (node (ref "Q30") (pin "D") (pinfunction "D_D") (pintype "passive"))
      (node (ref "Q31") (pin "D") (pinfunction "D_D") (pintype "passive"))
      (node (ref "Q32") (pin "D") (pinfunction "D_D") (pintype "passive"))
      (node (ref "Q33") (pin "D") (pinfunction "D_D") (pintype "passive"))
      (node (ref "Q34") (pin "D") (pinfunction "D_D") (pintype "passive"))
      (node (ref "Q35") (pin "D") (pinfunction "D_D") (pintype "passive"))
      (node (ref "Q36") (pin "D") (pinfunction "D_D") (pintype "passive"))
      (node (ref "Q38") (pin "D") (pinfunction "D_D") (pintype "passive"))
      (node (ref "Q39") (pin "D") (pinfunction "D_D") (pintype "passive"))
      (node (ref "Q40") (pin "D") (pinfunction "D_D") (pintype "passive"))
      (node (ref "Q41") (pin "D") (pinfunction "D_D") (pintype "passive"))
      (node (ref "Q42") (pin "D") (pinfunction "D_D") (pintype "passive"))
      (node (ref "Q43") (pin "D") (pinfunction "D_D") (pintype "passive"))
      (node (ref "Q44") (pin "D") (pinfunction "D_D") (pintype "passive"))
      (node (ref "Q45") (pin "D") (pinfunction "D_D") (pintype "passive"))
      (node (ref "Q46") (pin "D") (pinfunction "D_D") (pintype "passive"))
      (node (ref "Q47") (pin "D") (pinfunction "D_D") (pintype "passive"))
      (node (ref "Q48") (pin "D") (pinfunction "D_D") (pintype "passive"))
      (node (ref "X2") (pin "1") (pinfunction "KL_1") (pintype "passive"))
      (node (ref "X2") (pin "2") (pinfunction "KL_2") (pintype "passive"))
    )
    (net (code "132") (name "unconnected-(H25-MOUNT-PadB3,2)") (class "Default")
      (node (ref "H25") (pin "B3,2") (pinfunction "MOUNT_B3,2") (pintype "passive"))
    )
    (net (code "133") (name "unconnected-(Q1-EN-Pad5)") (class "Default")
      (node (ref "Q1") (pin "5") (pinfunction "EN_5") (pintype "output"))
    )
    (net (code "134") (name "unconnected-(Q2-EN-Pad5)") (class "Default")
      (node (ref "Q2") (pin "5") (pinfunction "EN_5") (pintype "output"))
    )
    (net (code "135") (name "unconnected-(Q14-EN-Pad5)") (class "Default")
      (node (ref "Q14") (pin "5") (pinfunction "EN_5") (pintype "output"))
    )
    (net (code "136") (name "unconnected-(Q37-EN-Pad5)") (class "Default")
      (node (ref "Q37") (pin "5") (pinfunction "EN_5") (pintype "output"))
    )
  )
)
